# 3KW-139_V1_2SchDoc.net
KiCad netlist of a schematic drawn in Altium Designer
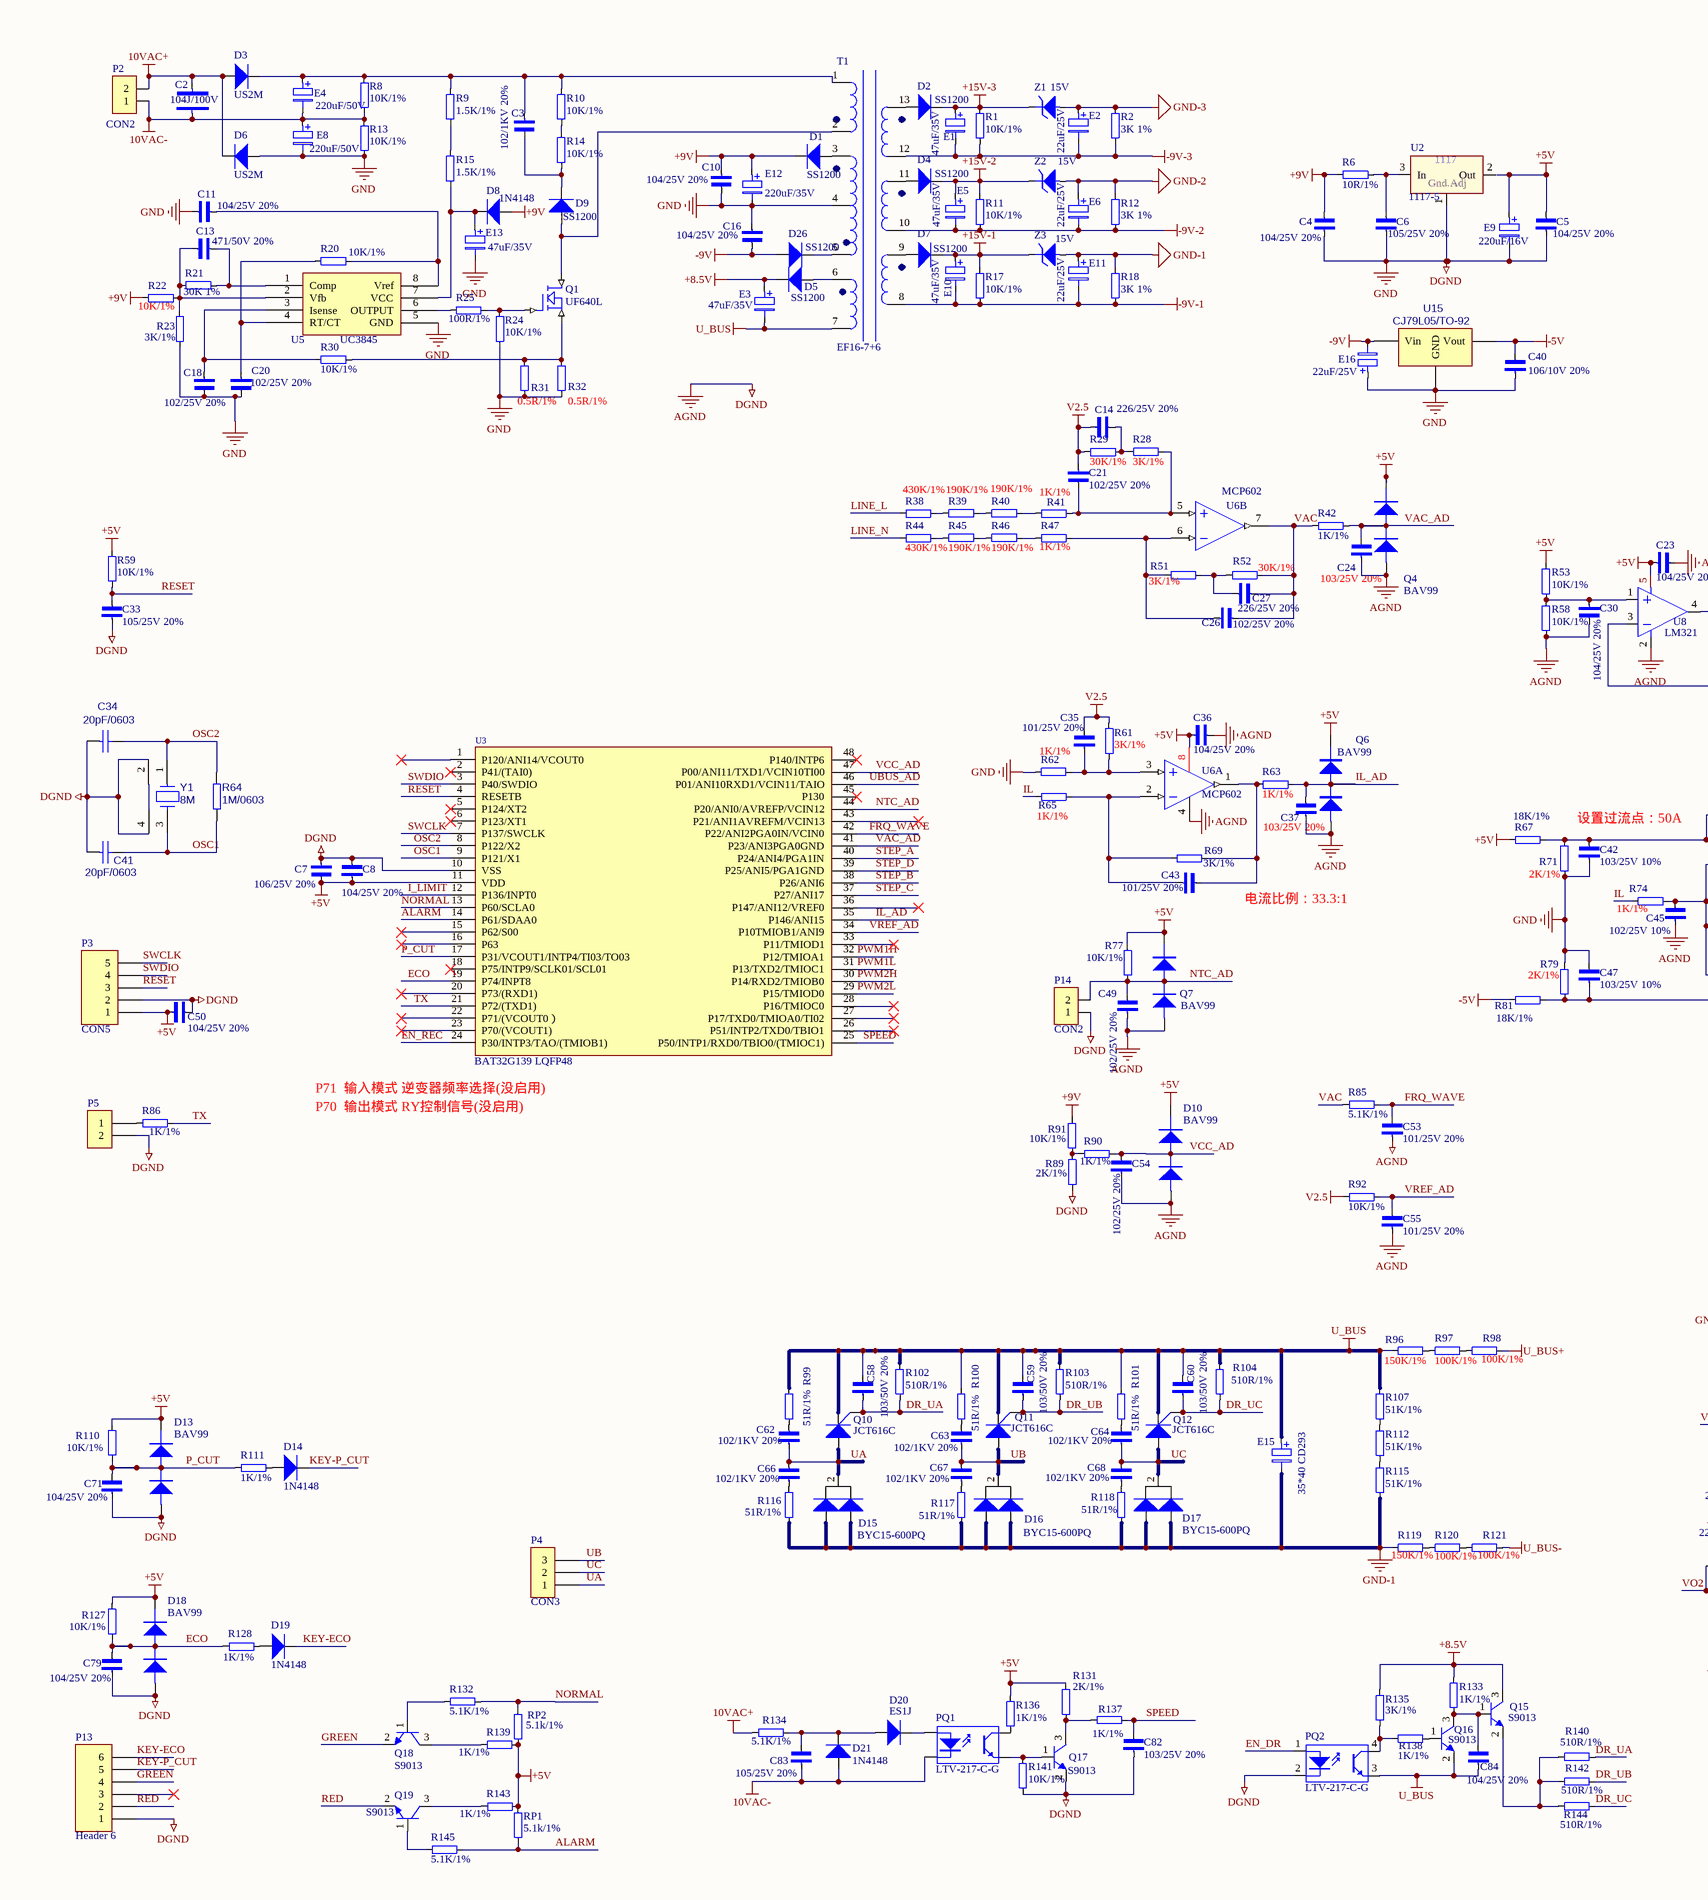
[diagram p0: 3KW-139_V1.2SchDoc.SchDoc, left]
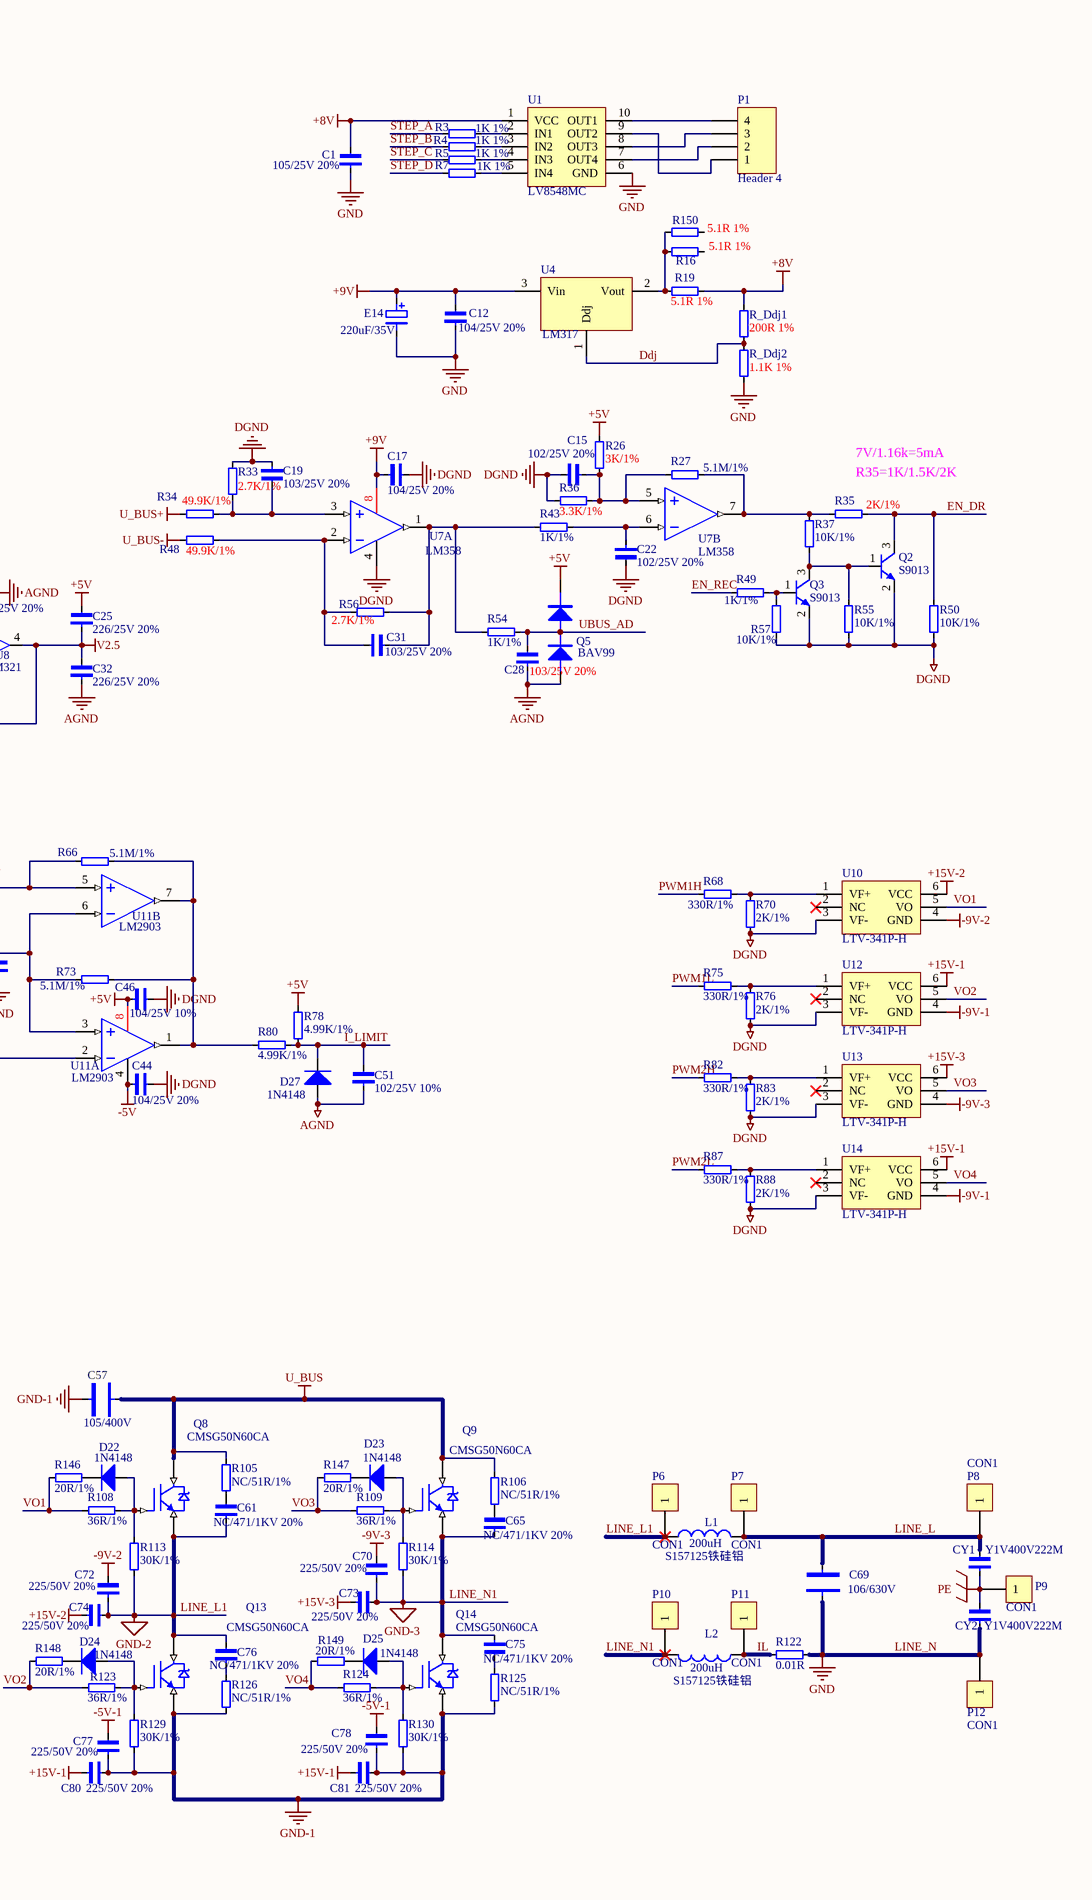
[diagram p1: 3KW-139_V1.2SchDoc.SchDoc, right]

(export (version "E")
  (design (tool "Eeschema 10.0.6"))
  (components
    (comp (ref "C1")
      (value "105/25V 20%")
      (footprint "0603c")
      (description "贴片 无极性电容")
      (libsource (lib "PCB_CMS_139") (part "C_SMD"))
    )
    (comp (ref "C2")
      (value "104J/100V")
      (footprint "104/100V")
      (description "CBB无极性电容")
      (libsource (lib "PCB_CMS_139") (part "CAPACITOR_CBB"))
    )
    (comp (ref "C3")
      (value "102/1KV 20%")
      (footprint "1206C")
      (description "贴片 无极性电容")
      (libsource (lib "PCB_CMS_139") (part "C_SMD"))
    )
    (comp (ref "C4")
      (value "104/25V 20%")
      (footprint "0603c")
      (description "贴片 无极性电容")
      (libsource (lib "PCB_CMS_139") (part "C_SMD"))
    )
    (comp (ref "C5")
      (value "104/25V 20%")
      (footprint "0603c")
      (description "贴片 无极性电容")
      (libsource (lib "PCB_CMS_139") (part "C_SMD"))
    )
    (comp (ref "C6")
      (value "105/25V 20%")
      (footprint "0603c")
      (description "贴片 无极性电容")
      (libsource (lib "PCB_CMS_139") (part "C_SMD"))
    )
    (comp (ref "C7")
      (value "106/25V 20%")
      (footprint "0603c")
      (description "贴片 无极性电容")
      (libsource (lib "PCB_CMS_139") (part "C_SMD"))
    )
    (comp (ref "C8")
      (value "104/25V 20%")
      (footprint "0603c")
      (description "贴片 无极性电容")
      (libsource (lib "PCB_CMS_139") (part "C_SMD"))
    )
    (comp (ref "C10")
      (value "104/25V 20%")
      (footprint "0603C")
      (description "贴片 无极性电容")
      (libsource (lib "PCB_CMS_139") (part "C_SMD"))
    )
    (comp (ref "C11")
      (value "104/25V 20%")
      (footprint "0603C")
      (description "贴片 无极性电容")
      (libsource (lib "PCB_CMS_139") (part "C_SMD"))
    )
    (comp (ref "C12")
      (value "104/25V 20%")
      (footprint "0603c")
      (description "贴片 无极性电容")
      (libsource (lib "PCB_CMS_139") (part "C_SMD"))
    )
    (comp (ref "C13")
      (value "471/50V 20%")
      (footprint "0603C")
      (description "贴片 无极性电容")
      (libsource (lib "PCB_CMS_139") (part "C_SMD"))
    )
    (comp (ref "C14")
      (value "226/25V 20%")
      (footprint "0603c")
      (description "贴片 无极性电容")
      (libsource (lib "PCB_CMS_139") (part "C_SMD"))
    )
    (comp (ref "C15")
      (value "102/25V 20%")
      (footprint "0603c")
      (description "贴片 无极性电容")
      (libsource (lib "PCB_CMS_139") (part "C_SMD"))
    )
    (comp (ref "C16")
      (value "104/25V 20%")
      (footprint "0603C")
      (description "贴片 无极性电容")
      (libsource (lib "PCB_CMS_139") (part "C_SMD"))
    )
    (comp (ref "C17")
      (value "104/25V 20%")
      (footprint "0603c")
      (description "贴片 无极性电容")
      (libsource (lib "PCB_CMS_139") (part "C_SMD"))
    )
    (comp (ref "C18")
      (value "102/25V 20%")
      (footprint "0603C")
      (description "贴片 无极性电容")
      (libsource (lib "PCB_CMS_139") (part "C_SMD"))
    )
    (comp (ref "C19")
      (value "103/25V 20%")
      (footprint "0603c")
      (description "贴片 无极性电容")
      (libsource (lib "PCB_CMS_139") (part "C_SMD"))
    )
    (comp (ref "C20")
      (value "102/25V 20%")
      (footprint "0603C")
      (description "贴片 无极性电容")
      (libsource (lib "PCB_CMS_139") (part "C_SMD"))
    )
    (comp (ref "C21")
      (value "102/25V 20%")
      (footprint "0603c")
      (description "贴片 无极性电容")
      (libsource (lib "PCB_CMS_139") (part "C_SMD"))
    )
    (comp (ref "C22")
      (value "102/25V 20%")
      (footprint "0603c")
      (description "贴片 无极性电容")
      (libsource (lib "PCB_CMS_139") (part "C_SMD"))
    )
    (comp (ref "C23")
      (value "104/25V 20%")
      (footprint "0603c")
      (description "贴片 无极性电容")
      (libsource (lib "PCB_CMS_139") (part "C_SMD"))
    )
    (comp (ref "C24")
      (value "103/25V 20%")
      (footprint "0603c")
      (description "贴片 无极性电容")
      (libsource (lib "PCB_CMS_139") (part "C_SMD"))
    )
    (comp (ref "C25")
      (value "226/25V 20%")
      (footprint "0603c")
      (description "贴片 无极性电容")
      (libsource (lib "PCB_CMS_139") (part "C_SMD"))
    )
    (comp (ref "C26")
      (value "102/25V 20%")
      (footprint "0603c")
      (description "贴片 无极性电容")
      (libsource (lib "PCB_CMS_139") (part "C_SMD"))
    )
    (comp (ref "C27")
      (value "226/25V 20%")
      (footprint "0603c")
      (description "贴片 无极性电容")
      (libsource (lib "PCB_CMS_139") (part "C_SMD"))
    )
    (comp (ref "C28")
      (value "103/25V 20%")
      (footprint "0603c")
      (description "贴片 无极性电容")
      (libsource (lib "PCB_CMS_139") (part "C_SMD"))
    )
    (comp (ref "C30")
      (value "104/25V 20%")
      (footprint "0603c")
      (description "贴片 无极性电容")
      (libsource (lib "PCB_CMS_139") (part "C_SMD"))
    )
    (comp (ref "C31")
      (value "103/25V 20%")
      (footprint "0603c")
      (description "贴片 无极性电容")
      (libsource (lib "PCB_CMS_139") (part "C_SMD"))
    )
    (comp (ref "C32")
      (value "226/25V 20%")
      (footprint "0603c")
      (description "贴片 无极性电容")
      (libsource (lib "PCB_CMS_139") (part "C_SMD"))
    )
    (comp (ref "C33")
      (value "105/25V 20%")
      (footprint "0603c")
      (description "贴片 无极性电容")
      (libsource (lib "PCB_CMS_139") (part "C_SMD"))
    )
    (comp (ref "C34")
      (value "20pF/0603")
      (footprint "C0603")
      (description "Cap")
      (libsource (lib "*") (part "CAP-SMD"))
    )
    (comp (ref "C35")
      (value "101/25V 20%")
      (footprint "0603c")
      (description "贴片 无极性电容")
      (libsource (lib "PCB_CMS_139") (part "C_SMD"))
    )
    (comp (ref "C36")
      (value "104/25V 20%")
      (footprint "0603c")
      (description "贴片 无极性电容")
      (libsource (lib "PCB_CMS_139") (part "C_SMD"))
    )
    (comp (ref "C37")
      (value "103/25V 20%")
      (footprint "0603c")
      (description "贴片 无极性电容")
      (libsource (lib "PCB_CMS_139") (part "C_SMD"))
    )
    (comp (ref "C40")
      (value "106/10V 20%")
      (footprint "0603c")
      (description "贴片 无极性电容")
      (libsource (lib "PCB_CMS_139") (part "C_SMD"))
    )
    (comp (ref "C41")
      (value "20pF/0603")
      (footprint "C0603")
      (description "Cap")
      (libsource (lib "*") (part "CAP-SMD"))
    )
    (comp (ref "C42")
      (value "103/25V 10%")
      (footprint "0603c")
      (description "贴片 无极性电容")
      (libsource (lib "PCB_CMS_139") (part "C_SMD"))
    )
    (comp (ref "C43")
      (value "101/25V 20%")
      (footprint "0603c")
      (description "贴片 无极性电容")
      (libsource (lib "PCB_CMS_139") (part "C_SMD"))
    )
    (comp (ref "C44")
      (value "104/25V 20%")
      (footprint "0603c")
      (description "贴片 无极性电容")
      (libsource (lib "PCB_CMS_139") (part "C_SMD"))
    )
    (comp (ref "C45")
      (value "102/25V 10%")
      (footprint "0603c")
      (description "贴片 无极性电容")
      (libsource (lib "PCB_CMS_139") (part "C_SMD"))
    )
    (comp (ref "C46")
      (value "104/25V 10%")
      (footprint "0603c")
      (description "贴片 无极性电容")
      (libsource (lib "PCB_CMS_139") (part "C_SMD"))
    )
    (comp (ref "C47")
      (value "103/25V 10%")
      (footprint "0603c")
      (description "贴片 无极性电容")
      (libsource (lib "PCB_CMS_139") (part "C_SMD"))
    )
    (comp (ref "C49")
      (value "102/25V 20%")
      (footprint "0603c")
      (description "贴片 无极性电容")
      (libsource (lib "PCB_CMS_139") (part "C_SMD"))
    )
    (comp (ref "C50")
      (value "104/25V 20%")
      (footprint "0603c")
      (description "贴片 无极性电容")
      (libsource (lib "PCB_CMS_139") (part "C_SMD"))
    )
    (comp (ref "C51")
      (value "102/25V 10%")
      (footprint "0603c")
      (description "贴片 无极性电容")
      (libsource (lib "PCB_CMS_139") (part "C_SMD"))
    )
    (comp (ref "C53")
      (value "101/25V 20%")
      (footprint "0603c")
      (description "贴片 无极性电容")
      (libsource (lib "PCB_CMS_139") (part "C_SMD"))
    )
    (comp (ref "C54")
      (value "102/25V 20%")
      (footprint "0603C")
      (description "贴片 无极性电容")
      (libsource (lib "PCB_CMS_139") (part "C_SMD"))
    )
    (comp (ref "C55")
      (value "101/25V 20%")
      (footprint "0603c")
      (description "贴片 无极性电容")
      (libsource (lib "PCB_CMS_139") (part "C_SMD"))
    )
    (comp (ref "C57")
      (value "105/400V")
      (footprint "105/400V-3")
      (description "CBB无极性电容")
      (libsource (lib "PCB_CMS_139") (part "CAPACITOR_CBB"))
    )
    (comp (ref "C58")
      (value "103/50V 20%")
      (footprint "1206C")
      (description "贴片 无极性电容")
      (libsource (lib "PCB_CMS_139") (part "C_SMD"))
    )
    (comp (ref "C59")
      (value "103/50V 20%")
      (footprint "1206C")
      (description "贴片 无极性电容")
      (libsource (lib "PCB_CMS_139") (part "C_SMD"))
    )
    (comp (ref "C60")
      (value "103/50V 20%")
      (footprint "1206C")
      (description "贴片 无极性电容")
      (libsource (lib "PCB_CMS_139") (part "C_SMD"))
    )
    (comp (ref "C61")
      (value "NC/471/1KV 20%")
      (footprint "1206C")
      (description "贴片 无极性电容")
      (libsource (lib "PCB_CMS_139") (part "C_SMD"))
    )
    (comp (ref "C62")
      (value "102/1KV 20%")
      (footprint "1206C")
      (description "贴片 无极性电容")
      (libsource (lib "PCB_CMS_139") (part "C_SMD"))
    )
    (comp (ref "C63")
      (value "102/1KV 20%")
      (footprint "1206C")
      (description "贴片 无极性电容")
      (libsource (lib "PCB_CMS_139") (part "C_SMD"))
    )
    (comp (ref "C64")
      (value "102/1KV 20%")
      (footprint "1206C")
      (description "贴片 无极性电容")
      (libsource (lib "PCB_CMS_139") (part "C_SMD"))
    )
    (comp (ref "C65")
      (value "NC/471/1KV 20%")
      (footprint "1206C")
      (description "贴片 无极性电容")
      (libsource (lib "PCB_CMS_139") (part "C_SMD"))
    )
    (comp (ref "C66")
      (value "102/1KV 20%")
      (footprint "1206C")
      (description "贴片 无极性电容")
      (libsource (lib "PCB_CMS_139") (part "C_SMD"))
    )
    (comp (ref "C67")
      (value "102/1KV 20%")
      (footprint "1206C")
      (description "贴片 无极性电容")
      (libsource (lib "PCB_CMS_139") (part "C_SMD"))
    )
    (comp (ref "C68")
      (value "102/1KV 20%")
      (footprint "1206C")
      (description "贴片 无极性电容")
      (libsource (lib "PCB_CMS_139") (part "C_SMD"))
    )
    (comp (ref "C69")
      (value "106/630V")
      (footprint "106/400V")
      (description "CBB无极性电容")
      (libsource (lib "PCB_CMS_139") (part "CAPACITOR_CBB"))
    )
    (comp (ref "C70")
      (value "225/50V 20%")
      (footprint "1206C")
      (description "贴片 无极性电容")
      (libsource (lib "PCB_CMS_139") (part "C_SMD"))
    )
    (comp (ref "C71")
      (value "104/25V 20%")
      (footprint "0603C")
      (description "贴片 无极性电容")
      (libsource (lib "PCB_CMS_139") (part "C_SMD"))
    )
    (comp (ref "C72")
      (value "225/50V 20%")
      (footprint "1206C")
      (description "贴片 无极性电容")
      (libsource (lib "PCB_CMS_139") (part "C_SMD"))
    )
    (comp (ref "C73")
      (value "225/50V 20%")
      (footprint "1206C")
      (description "贴片 无极性电容")
      (libsource (lib "PCB_CMS_139") (part "C_SMD"))
    )
    (comp (ref "C74")
      (value "225/50V 20%")
      (footprint "1206C")
      (description "贴片 无极性电容")
      (libsource (lib "PCB_CMS_139") (part "C_SMD"))
    )
    (comp (ref "C75")
      (value "NC/471/1KV 20%")
      (footprint "1206C")
      (description "贴片 无极性电容")
      (libsource (lib "PCB_CMS_139") (part "C_SMD"))
    )
    (comp (ref "C76")
      (value "NC/471/1KV 20%")
      (footprint "1206C")
      (description "贴片 无极性电容")
      (libsource (lib "PCB_CMS_139") (part "C_SMD"))
    )
    (comp (ref "C77")
      (value "225/50V 20%")
      (footprint "1206C")
      (description "贴片 无极性电容")
      (libsource (lib "PCB_CMS_139") (part "C_SMD"))
    )
    (comp (ref "C78")
      (value "225/50V 20%")
      (footprint "1206C")
      (description "贴片 无极性电容")
      (libsource (lib "PCB_CMS_139") (part "C_SMD"))
    )
    (comp (ref "C79")
      (value "104/25V 20%")
      (footprint "0603C")
      (description "贴片 无极性电容")
      (libsource (lib "PCB_CMS_139") (part "C_SMD"))
    )
    (comp (ref "C80")
      (value "225/50V 20%")
      (footprint "1206C")
      (description "贴片 无极性电容")
      (libsource (lib "PCB_CMS_139") (part "C_SMD"))
    )
    (comp (ref "C81")
      (value "225/50V 20%")
      (footprint "1206C")
      (description "贴片 无极性电容")
      (libsource (lib "PCB_CMS_139") (part "C_SMD"))
    )
    (comp (ref "C82")
      (value "103/25V 20%")
      (footprint "0603C")
      (description "贴片 无极性电容")
      (libsource (lib "PCB_CMS_139") (part "C_SMD"))
    )
    (comp (ref "C83")
      (value "105/25V 20%")
      (footprint "1206C")
      (description "贴片 无极性电容")
      (libsource (lib "PCB_CMS_139") (part "C_SMD"))
    )
    (comp (ref "C84")
      (value "104/25V 20%")
      (footprint "1206C")
      (description "贴片 无极性电容")
      (libsource (lib "PCB_CMS_139") (part "C_SMD"))
    )
    (comp (ref "CY1")
      (value "Y1V400V222M")
      (footprint "Y1V400")
      (description "贴片 无极性电容")
      (libsource (lib "PCB_CMS_139") (part "C_SMD"))
    )
    (comp (ref "CY2")
      (value "Y1V400V222M")
      (footprint "Y1V400")
      (description "贴片 无极性电容")
      (libsource (lib "PCB_CMS_139") (part "C_SMD"))
    )
    (comp (ref "D1")
      (value "SS1200")
      (footprint "SMA - AK")
      (description "贴片 二极管")
      (libsource (lib "PCB_CMS_139") (part "D_SMD"))
    )
    (comp (ref "D2")
      (value "SS1200")
      (footprint "SMA - AK")
      (description "贴片 二极管")
      (libsource (lib "PCB_CMS_139") (part "D_SMD"))
    )
    (comp (ref "D3")
      (value "US2M")
      (footprint "SMA - AK")
      (description "贴片 二极管")
      (libsource (lib "PCB_CMS_139") (part "D_SMD"))
    )
    (comp (ref "D4")
      (value "SS1200")
      (footprint "SMA - AK")
      (description "贴片 二极管")
      (libsource (lib "PCB_CMS_139") (part "D_SMD"))
    )
    (comp (ref "D5")
      (value "SS1200")
      (footprint "SMA - AK")
      (description "贴片 二极管")
      (libsource (lib "PCB_CMS_139") (part "D_SMD"))
    )
    (comp (ref "D6")
      (value "US2M")
      (footprint "SMA - AK")
      (description "贴片 二极管")
      (libsource (lib "PCB_CMS_139") (part "D_SMD"))
    )
    (comp (ref "D7")
      (value "SS1200")
      (footprint "SMA - AK")
      (description "贴片 二极管")
      (libsource (lib "PCB_CMS_139") (part "D_SMD"))
    )
    (comp (ref "D8")
      (value "1N4148")
      (footprint "SOD-123F")
      (description "贴片 二极管")
      (libsource (lib "PCB_CMS_139") (part "D_SMD"))
    )
    (comp (ref "D9")
      (value "SS1200")
      (footprint "SMA - AK")
      (description "贴片 二极管")
      (libsource (lib "PCB_CMS_139") (part "D_SMD"))
    )
    (comp (ref "D10")
      (value "BAV99")
      (footprint "SOT-23")
      (description "贴片串联双二极管 eg:BAT54S")
      (libsource (lib "PCB_CMS_139") (part "D2-串联"))
    )
    (comp (ref "D13")
      (value "BAV99")
      (footprint "SOT-23")
      (description "贴片串联双二极管 eg:BAT54S")
      (libsource (lib "PCB_CMS_139") (part "D2-串联"))
    )
    (comp (ref "D14")
      (value "1N4148")
      (footprint "SOD-123F")
      (description "贴片 二极管")
      (libsource (lib "PCB_CMS_139") (part "D_SMD"))
    )
    (comp (ref "D15")
      (value "BYC15-600PQ")
      (footprint "TO-220-AC - S")
      (libsource (lib "PCB_CMS_139") (part "DIODE TO-220"))
    )
    (comp (ref "D16")
      (value "BYC15-600PQ")
      (footprint "TO-220-AC - S")
      (libsource (lib "PCB_CMS_139") (part "DIODE TO-220"))
    )
    (comp (ref "D17")
      (value "BYC15-600PQ")
      (footprint "TO-220-AC - S")
      (libsource (lib "PCB_CMS_139") (part "DIODE TO-220"))
    )
    (comp (ref "D18")
      (value "BAV99")
      (footprint "SOT-23")
      (description "贴片串联双二极管 eg:BAT54S")
      (libsource (lib "PCB_CMS_139") (part "D2-串联"))
    )
    (comp (ref "D19")
      (value "1N4148")
      (footprint "SOD-123F")
      (description "贴片 二极管")
      (libsource (lib "PCB_CMS_139") (part "D_SMD"))
    )
    (comp (ref "D20")
      (value "ES1J")
      (footprint "SOD-123F")
      (description "贴片 二极管")
      (libsource (lib "PCB_CMS_139") (part "D_SMD"))
    )
    (comp (ref "D21")
      (value "1N4148")
      (footprint "SOD-123F")
      (description "贴片 二极管")
      (libsource (lib "PCB_CMS_139") (part "D_SMD"))
    )
    (comp (ref "D22")
      (value "1N4148")
      (footprint "SOD-123F")
      (description "贴片 二极管")
      (libsource (lib "PCB_CMS_139") (part "D_SMD"))
    )
    (comp (ref "D23")
      (value "1N4148")
      (footprint "SOD-123F")
      (description "贴片 二极管")
      (libsource (lib "PCB_CMS_139") (part "D_SMD"))
    )
    (comp (ref "D24")
      (value "1N4148")
      (footprint "SOD-123F")
      (description "贴片 二极管")
      (libsource (lib "PCB_CMS_139") (part "D_SMD"))
    )
    (comp (ref "D25")
      (value "1N4148")
      (footprint "SOD-123F")
      (description "贴片 二极管")
      (libsource (lib "PCB_CMS_139") (part "D_SMD"))
    )
    (comp (ref "D26")
      (value "SS1200")
      (footprint "SMA - AK")
      (description "贴片 二极管")
      (libsource (lib "PCB_CMS_139") (part "D_SMD"))
    )
    (comp (ref "D27")
      (value "1N4148")
      (footprint "SOD-123F")
      (description "贴片 二极管")
      (libsource (lib "PCB_CMS_139") (part "D_SMD"))
    )
    (comp (ref "E1")
      (value "47uF/35V")
      (footprint "ECAP-6.3*11")
      (description "直插 电解电容")
      (libsource (lib "motor_sch") (part "E"))
    )
    (comp (ref "E2")
      (value "22uF/25V")
      (footprint "ECAP-5*11")
      (description "直插 电解电容")
      (libsource (lib "motor_sch") (part "E"))
    )
    (comp (ref "E3")
      (value "47uF/35V")
      (footprint "ECAP-6.3*11")
      (description "直插 电解电容")
      (libsource (lib "motor_sch") (part "E"))
    )
    (comp (ref "E4")
      (value "220uF/50V")
      (footprint "10*16")
      (description "直插 电解电容")
      (libsource (lib "motor_sch") (part "E"))
    )
    (comp (ref "E5")
      (value "47uF/35V")
      (footprint "ECAP-6.3*11")
      (description "直插 电解电容")
      (libsource (lib "motor_sch") (part "E"))
    )
    (comp (ref "E6")
      (value "22uF/25V")
      (footprint "ECAP-5*11")
      (description "直插 电解电容")
      (libsource (lib "motor_sch") (part "E"))
    )
    (comp (ref "E8")
      (value "220uF/50V")
      (footprint "10*16")
      (description "直插 电解电容")
      (libsource (lib "motor_sch") (part "E"))
    )
    (comp (ref "E9")
      (value "220uF/16V")
      (footprint "6.3*11")
      (description "直插 电解电容")
      (libsource (lib "motor_sch") (part "E"))
    )
    (comp (ref "E10")
      (value "47uF/35V")
      (footprint "ECAP-6.3*11")
      (description "直插 电解电容")
      (libsource (lib "motor_sch") (part "E"))
    )
    (comp (ref "E11")
      (value "22uF/25V")
      (footprint "ECAP-5*11")
      (description "直插 电解电容")
      (libsource (lib "motor_sch") (part "E"))
    )
    (comp (ref "E12")
      (value "220uF/35V")
      (footprint "8*12")
      (description "直插 电解电容")
      (libsource (lib "motor_sch") (part "E"))
    )
    (comp (ref "E13")
      (value "47uF/35V")
      (footprint "ECAP-6.3*11")
      (description "直插 电解电容")
      (libsource (lib "motor_sch") (part "E"))
    )
    (comp (ref "E14")
      (value "220uF/35V")
      (footprint "EC08F350")
      (description "直插 电解电容")
      (libsource (lib "motor_sch") (part "E"))
    )
    (comp (ref "E15")
      (value "35*40 CD293")
      (footprint "1000uF/250V")
      (description "直插 电解电容 35*40 CD293\r\n120VAC=2200uF/250V\r\n230VAC=330uF/450V")
      (libsource (lib "motor_sch") (part "E"))
    )
    (comp (ref "E16")
      (value "22uF/25V")
      (footprint "ECAP-5*11")
      (description "直插 电解电容")
      (libsource (lib "") (part "E_1"))
    )
    (comp (ref "L1")
      (value "S157125铁硅铝")
      (footprint "L45*45-1-1")
      (description "Inductor")
      (fields (field (name "ALTIUM_VALUE") "200uH") (field (name "PUBLISHER") "Altium Limited"))
      (libsource (lib "Miscellaneous Devices") (part "Inductor"))
    )
    (comp (ref "L2")
      (value "S157125铁硅铝")
      (footprint "L45*45-1-1")
      (description "Inductor")
      (fields (field (name "ALTIUM_VALUE") "200uH") (field (name "PUBLISHER") "Altium Limited"))
      (libsource (lib "Miscellaneous Devices") (part "Inductor"))
    )
    (comp (ref "P1")
      (value "Header 4")
      (footprint "P4-2.8")
      (description "Header, 4-Pin")
      (fields (field (name "PUBLISHER") "Altium Limited"))
      (libsource (lib "motor_sch-2017-6-15") (part "Header 4"))
    )
    (comp (ref "P2") (value "CON2") (footprint "DJ7021A-2.8-11") (libsource (lib "SCH") (part "CON2")))
    (comp (ref "P3")
      (value "CON5")
      (footprint "HDR1X5")
      (description "Header, 5-Pin")
      (fields (field (name "PUBLISHER") "Altium Limited"))
      (libsource (lib "motor_sch-2017-6-15") (part "Header 5"))
    )
    (comp (ref "P4") (value "CON3") (footprint "DJ3071A-6.3-11") (libsource (lib "SCH") (part "CON3")))
    (comp (ref "P5")
      (value "~")
      (footprint "mixic_motor_Library_V1.1:HDR1X2")
      (description "Connector, 2Pin")
      (libsource (lib "Gpower_Altium") (part "CON2P"))
    )
    (comp (ref "P6") (value "CON1") (footprint "HOLE1.0") (libsource (lib "SCH") (part "CON1")))
    (comp (ref "P7") (value "CON1") (footprint "HOLE1.0") (libsource (lib "SCH") (part "CON1")))
    (comp (ref "P8") (value "CON1") (footprint "HOLE2.5") (libsource (lib "SCH") (part "CON1")))
    (comp (ref "P9") (value "CON1") (footprint "HOLE1.6") (libsource (lib "") (part "CON1_1")))
    (comp (ref "P10") (value "CON1") (footprint "HOLE1.0") (libsource (lib "SCH") (part "CON1")))
    (comp (ref "P11") (value "CON1") (footprint "HOLE1.0") (libsource (lib "SCH") (part "CON1")))
    (comp (ref "P12") (value "CON1") (footprint "HOLE2.5") (libsource (lib "") (part "CON1_2")))
    (comp (ref "P13")
      (value "Header 6")
      (footprint "P6-2.8")
      (description "Header, 5-Pin")
      (fields (field (name "PUBLISHER") "Altium Limited"))
      (libsource (lib "motor_sch-2017-6-15") (part "Header 6"))
    )
    (comp (ref "P14") (value "CON2") (footprint "HDR1X2") (libsource (lib "SCH") (part "CON2")))
    (comp (ref "PQ1")
      (value "LTV-217-C-G")
      (footprint "SOP-4-P1.27")
      (description "光藕-PC817,PC357")
      (libsource (lib "GCE-SCH(2014.02.14)") (part "OPTO-817"))
    )
    (comp (ref "PQ2")
      (value "LTV-217-C-G")
      (footprint "SOP-4-P1.27")
      (description "光藕-PC817,PC357")
      (libsource (lib "") (part "OPTO-817_1"))
    )
    (comp (ref "Q1")
      (value "UF640L")
      (footprint "TO-220")
      (description "MOSFET")
      (libsource (lib "motor_sch-2017-6-15") (part "MOS-N"))
    )
    (comp (ref "Q2")
      (value "S9013")
      (footprint "S8050")
      (description "NPN")
      (libsource (lib "motor_sch-2017-6-15") (part "S8050"))
    )
    (comp (ref "Q3")
      (value "S9013")
      (footprint "S8050")
      (description "NPN")
      (libsource (lib "motor_sch-2017-6-15") (part "S8050"))
    )
    (comp (ref "Q4") (value "BAV99") (footprint "SOT-23") (libsource (lib "SCH") (part "BAV99")))
    (comp (ref "Q5") (value "BAV99") (footprint "SOT-23") (libsource (lib "SCH") (part "BAV99")))
    (comp (ref "Q6") (value "BAV99") (footprint "SOT-23") (libsource (lib "SCH") (part "BAV99")))
    (comp (ref "Q7") (value "BAV99") (footprint "SOT-23") (libsource (lib "SCH") (part "BAV99")))
    (comp (ref "Q8") (value "CMSG50N60CA") (footprint "to-247-1-1") (libsource (lib "Schlib1") (part "IGBT")))
    (comp (ref "Q9") (value "CMSG50N60CA") (footprint "to-247-1-1") (libsource (lib "Schlib1") (part "IGBT")))
    (comp (ref "Q10")
      (value "JCT616C")
      (footprint "TO-220-AB1 - S")
      (libsource (lib "PCB_CMS_139") (part "TYN625"))
    )
    (comp (ref "Q11")
      (value "JCT616C")
      (footprint "TO-220-AB1 - S")
      (libsource (lib "PCB_CMS_139") (part "TYN625"))
    )
    (comp (ref "Q12")
      (value "JCT616C")
      (footprint "TO-220-AB1 - S")
      (libsource (lib "PCB_CMS_139") (part "TYN625"))
    )
    (comp (ref "Q13")
      (value "CMSG50N60CA")
      (footprint "to-247-1-1")
      (libsource (lib "Schlib1") (part "IGBT"))
    )
    (comp (ref "Q14")
      (value "CMSG50N60CA")
      (footprint "to-247-1-1")
      (libsource (lib "Schlib1") (part "IGBT"))
    )
    (comp (ref "Q15")
      (value "S9013")
      (footprint "S8050")
      (description "NPN")
      (libsource (lib "motor_sch-2017-6-15") (part "S8050"))
    )
    (comp (ref "Q16")
      (value "S9013")
      (footprint "S8050")
      (description "NPN")
      (libsource (lib "motor_sch-2017-6-15") (part "S8050"))
    )
    (comp (ref "Q17")
      (value "S9013")
      (footprint "S8050")
      (description "NPN")
      (libsource (lib "motor_sch-2017-6-15") (part "S8050"))
    )
    (comp (ref "Q18")
      (value "S9013")
      (footprint "S8050")
      (description "NPN")
      (libsource (lib "motor_sch-2017-6-15") (part "S8050"))
    )
    (comp (ref "Q19")
      (value "S9013")
      (footprint "S8050")
      (description "NPN")
      (libsource (lib "motor_sch-2017-6-15") (part "S8050"))
    )
    (comp (ref "R1")
      (value "10K/1%")
      (footprint "0603R")
      (description "贴片 电阻器")
      (libsource (lib "PCB_CMS_139") (part "R_SMD"))
    )
    (comp (ref "R2")
      (value "3K 1%")
      (footprint "0603R")
      (description "贴片 电阻器")
      (libsource (lib "PCB_CMS_139") (part "R_SMD"))
    )
    (comp (ref "R3")
      (value "1K 1%")
      (footprint "0603R")
      (description "贴片 电阻器")
      (libsource (lib "PCB_CMS_139") (part "R_SMD"))
    )
    (comp (ref "R4")
      (value "1K 1%")
      (footprint "0603R")
      (description "贴片 电阻器")
      (libsource (lib "PCB_CMS_139") (part "R_SMD"))
    )
    (comp (ref "R5")
      (value "1K 1%")
      (footprint "0603R")
      (description "贴片 电阻器")
      (libsource (lib "PCB_CMS_139") (part "R_SMD"))
    )
    (comp (ref "R6")
      (value "10R/1%")
      (footprint "0603R")
      (description "贴片 电阻器")
      (libsource (lib "PCB_CMS_139") (part "R_SMD"))
    )
    (comp (ref "R7")
      (value "1K 1%")
      (footprint "0603R")
      (description "贴片 电阻器")
      (libsource (lib "PCB_CMS_139") (part "R_SMD"))
    )
    (comp (ref "R8")
      (value "10K/1%")
      (footprint "0603R")
      (description "贴片 电阻器")
      (libsource (lib "PCB_CMS_139") (part "R_SMD"))
    )
    (comp (ref "R9")
      (value "1.5K/1%")
      (footprint "1206R")
      (description "贴片 电阻器")
      (libsource (lib "PCB_CMS_139") (part "R_SMD"))
    )
    (comp (ref "R10")
      (value "10K/1%")
      (footprint "1206R")
      (description "贴片 电阻器")
      (libsource (lib "PCB_CMS_139") (part "R_SMD"))
    )
    (comp (ref "R11")
      (value "10K/1%")
      (footprint "0603R")
      (description "贴片 电阻器")
      (libsource (lib "PCB_CMS_139") (part "R_SMD"))
    )
    (comp (ref "R12")
      (value "3K 1%")
      (footprint "0603R")
      (description "贴片 电阻器")
      (libsource (lib "PCB_CMS_139") (part "R_SMD"))
    )
    (comp (ref "R13")
      (value "10K/1%")
      (footprint "0603R")
      (description "贴片 电阻器")
      (libsource (lib "PCB_CMS_139") (part "R_SMD"))
    )
    (comp (ref "R14")
      (value "10K/1%")
      (footprint "1206R")
      (description "贴片 电阻器")
      (libsource (lib "PCB_CMS_139") (part "R_SMD"))
    )
    (comp (ref "R15")
      (value "1.5K/1%")
      (footprint "1206R")
      (description "贴片 电阻器")
      (libsource (lib "PCB_CMS_139") (part "R_SMD"))
    )
    (comp (ref "R16")
      (value "5.1R 1%")
      (footprint "1206R")
      (description "贴片 电阻器")
      (libsource (lib "PCB_CMS_139") (part "R_SMD"))
    )
    (comp (ref "R17")
      (value "10K/1%")
      (footprint "0603R")
      (description "贴片 电阻器")
      (libsource (lib "PCB_CMS_139") (part "R_SMD"))
    )
    (comp (ref "R18")
      (value "3K 1%")
      (footprint "0603R")
      (description "贴片 电阻器")
      (libsource (lib "PCB_CMS_139") (part "R_SMD"))
    )
    (comp (ref "R19")
      (value "5.1R 1%")
      (footprint "1206R")
      (description "贴片 电阻器")
      (libsource (lib "PCB_CMS_139") (part "R_SMD"))
    )
    (comp (ref "R20")
      (value "10K/1%")
      (footprint "0603R")
      (description "贴片 电阻器")
      (libsource (lib "PCB_CMS_139") (part "R_SMD"))
    )
    (comp (ref "R21")
      (value "30K 1%")
      (footprint "0603R")
      (description "贴片 电阻器")
      (libsource (lib "PCB_CMS_139") (part "R_SMD"))
    )
    (comp (ref "R22")
      (value "10K/1%")
      (footprint "0603R")
      (description "贴片 电阻器")
      (libsource (lib "PCB_CMS_139") (part "R_SMD"))
    )
    (comp (ref "R23")
      (value "3K/1%")
      (footprint "0603R")
      (description "贴片 电阻器")
      (libsource (lib "PCB_CMS_139") (part "R_SMD"))
    )
    (comp (ref "R24")
      (value "10K/1%")
      (footprint "0603R")
      (description "贴片 电阻器")
      (libsource (lib "PCB_CMS_139") (part "R_SMD"))
    )
    (comp (ref "R25")
      (value "100R/1%")
      (footprint "0603R")
      (description "贴片 电阻器")
      (libsource (lib "PCB_CMS_139") (part "R_SMD"))
    )
    (comp (ref "R26")
      (value "3K/1%")
      (footprint "0603R")
      (description "贴片 电阻器")
      (libsource (lib "PCB_CMS_139") (part "R_SMD"))
    )
    (comp (ref "R27")
      (value "5.1M/1%")
      (footprint "0603R")
      (description "贴片 电阻器")
      (libsource (lib "PCB_CMS_139") (part "R_SMD"))
    )
    (comp (ref "R28")
      (value "3K/1%")
      (footprint "0603R")
      (description "贴片 电阻器")
      (libsource (lib "PCB_CMS_139") (part "R_SMD"))
    )
    (comp (ref "R29")
      (value "30K/1%")
      (footprint "0603R")
      (description "贴片 电阻器")
      (libsource (lib "PCB_CMS_139") (part "R_SMD"))
    )
    (comp (ref "R30")
      (value "10K/1%")
      (footprint "0603R")
      (description "贴片 电阻器")
      (libsource (lib "PCB_CMS_139") (part "R_SMD"))
    )
    (comp (ref "R31")
      (value "0.5R/1%")
      (footprint "1206R")
      (description "贴片 电阻器")
      (libsource (lib "PCB_CMS_139") (part "R_SMD"))
    )
    (comp (ref "R32")
      (value "0.5R/1%")
      (footprint "1206R")
      (description "贴片 电阻器")
      (libsource (lib "PCB_CMS_139") (part "R_SMD"))
    )
    (comp (ref "R33")
      (value "2.7K/1%")
      (footprint "0603R")
      (description "贴片 电阻器")
      (libsource (lib "PCB_CMS_139") (part "R_SMD"))
    )
    (comp (ref "R34")
      (value "49.9K/1%")
      (footprint "0603R")
      (description "贴片 电阻器")
      (libsource (lib "PCB_CMS_139") (part "R_SMD"))
    )
    (comp (ref "R35")
      (value "2K/1%")
      (footprint "0603R")
      (description "贴片 电阻器")
      (libsource (lib "PCB_CMS_139") (part "R_SMD"))
    )
    (comp (ref "R36")
      (value "3.3K/1%")
      (footprint "0603R")
      (description "贴片 电阻器")
      (libsource (lib "PCB_CMS_139") (part "R_SMD"))
    )
    (comp (ref "R37")
      (value "10K/1%")
      (footprint "0603R")
      (description "贴片 电阻器")
      (libsource (lib "PCB_CMS_139") (part "R_SMD"))
    )
    (comp (ref "R38")
      (value "430K/1%")
      (footprint "1206R")
      (description "贴片 电阻器")
      (libsource (lib "PCB_CMS_139") (part "R_SMD"))
    )
    (comp (ref "R39")
      (value "190K/1%")
      (footprint "1206R")
      (description "贴片 电阻器")
      (libsource (lib "PCB_CMS_139") (part "R_SMD"))
    )
    (comp (ref "R40")
      (value "190K/1%")
      (footprint "1206R")
      (description "贴片 电阻器")
      (libsource (lib "PCB_CMS_139") (part "R_SMD"))
    )
    (comp (ref "R41")
      (value "1K/1%")
      (footprint "0603R")
      (description "贴片 电阻器")
      (libsource (lib "PCB_CMS_139") (part "R_SMD"))
    )
    (comp (ref "R42")
      (value "1K/1%")
      (footprint "0603R")
      (description "贴片 电阻器")
      (libsource (lib "PCB_CMS_139") (part "R_SMD"))
    )
    (comp (ref "R43")
      (value "1K/1%")
      (footprint "0603R")
      (description "贴片 电阻器")
      (libsource (lib "PCB_CMS_139") (part "R_SMD"))
    )
    (comp (ref "R44")
      (value "430K/1%")
      (footprint "1206R")
      (description "贴片 电阻器")
      (libsource (lib "PCB_CMS_139") (part "R_SMD"))
    )
    (comp (ref "R45")
      (value "190K/1%")
      (footprint "1206R")
      (description "贴片 电阻器")
      (libsource (lib "PCB_CMS_139") (part "R_SMD"))
    )
    (comp (ref "R46")
      (value "190K/1%")
      (footprint "1206R")
      (description "贴片 电阻器")
      (libsource (lib "PCB_CMS_139") (part "R_SMD"))
    )
    (comp (ref "R47")
      (value "1K/1%")
      (footprint "0603R")
      (description "贴片 电阻器")
      (libsource (lib "PCB_CMS_139") (part "R_SMD"))
    )
    (comp (ref "R48")
      (value "49.9K/1%")
      (footprint "0603R")
      (description "贴片 电阻器")
      (libsource (lib "PCB_CMS_139") (part "R_SMD"))
    )
    (comp (ref "R49")
      (value "1K/1%")
      (footprint "0603R")
      (description "贴片 电阻器")
      (libsource (lib "PCB_CMS_139") (part "R_SMD"))
    )
    (comp (ref "R50")
      (value "10K/1%")
      (footprint "0603R")
      (description "贴片 电阻器")
      (libsource (lib "PCB_CMS_139") (part "R_SMD"))
    )
    (comp (ref "R51")
      (value "3K/1%")
      (footprint "0603R")
      (description "贴片 电阻器")
      (libsource (lib "PCB_CMS_139") (part "R_SMD"))
    )
    (comp (ref "R52")
      (value "30K/1%")
      (footprint "0603R")
      (description "贴片 电阻器")
      (libsource (lib "PCB_CMS_139") (part "R_SMD"))
    )
    (comp (ref "R53")
      (value "10K/1%")
      (footprint "0603R")
      (description "贴片 电阻器")
      (libsource (lib "PCB_CMS_139") (part "R_SMD"))
    )
    (comp (ref "R54")
      (value "1K/1%")
      (footprint "0603R")
      (description "贴片 电阻器")
      (libsource (lib "PCB_CMS_139") (part "R_SMD"))
    )
    (comp (ref "R55")
      (value "10K/1%")
      (footprint "0603R")
      (description "贴片 电阻器")
      (libsource (lib "PCB_CMS_139") (part "R_SMD"))
    )
    (comp (ref "R56")
      (value "2.7K/1%")
      (footprint "0603R")
      (description "贴片 电阻器")
      (libsource (lib "PCB_CMS_139") (part "R_SMD"))
    )
    (comp (ref "R57")
      (value "10K/1%")
      (footprint "0603R")
      (description "贴片 电阻器")
      (libsource (lib "PCB_CMS_139") (part "R_SMD"))
    )
    (comp (ref "R58")
      (value "10K/1%")
      (footprint "0603R")
      (description "贴片 电阻器")
      (libsource (lib "PCB_CMS_139") (part "R_SMD"))
    )
    (comp (ref "R59")
      (value "10K/1%")
      (footprint "0603R")
      (description "贴片 电阻器")
      (libsource (lib "PCB_CMS_139") (part "R_SMD"))
    )
    (comp (ref "R61")
      (value "3K/1%")
      (footprint "0603R")
      (description "贴片 电阻器")
      (libsource (lib "PCB_CMS_139") (part "R_SMD"))
    )
    (comp (ref "R62")
      (value "1K/1%")
      (footprint "0603R")
      (description "贴片 电阻器")
      (libsource (lib "PCB_CMS_139") (part "R_SMD"))
    )
    (comp (ref "R63")
      (value "1K/1%")
      (footprint "0603R")
      (description "贴片 电阻器")
      (libsource (lib "PCB_CMS_139") (part "R_SMD"))
    )
    (comp (ref "R64")
      (value "1M/0603")
      (footprint "R0603")
      (description "SMD")
      (libsource (lib "*") (part "RES-SMD"))
    )
    (comp (ref "R65")
      (value "1K/1%")
      (footprint "0603R")
      (description "贴片 电阻器")
      (libsource (lib "PCB_CMS_139") (part "R_SMD"))
    )
    (comp (ref "R66")
      (value "5.1M/1%")
      (footprint "0603R")
      (description "贴片 电阻器")
      (libsource (lib "PCB_CMS_139") (part "R_SMD"))
    )
    (comp (ref "R67")
      (value "18K/1%")
      (footprint "0603R")
      (description "贴片 电阻器")
      (libsource (lib "PCB_CMS_139") (part "R_SMD"))
    )
    (comp (ref "R68")
      (value "330R/1%")
      (footprint "0603R")
      (description "贴片 电阻器")
      (libsource (lib "PCB_CMS_139") (part "R_SMD"))
    )
    (comp (ref "R69")
      (value "3K/1%")
      (footprint "0603R")
      (description "贴片 电阻器")
      (libsource (lib "PCB_CMS_139") (part "R_SMD"))
    )
    (comp (ref "R70")
      (value "2K/1%")
      (footprint "0603R")
      (description "贴片 电阻器")
      (libsource (lib "PCB_CMS_139") (part "R_SMD"))
    )
    (comp (ref "R71")
      (value "2K/1%")
      (footprint "0603R")
      (description "贴片 电阻器")
      (libsource (lib "PCB_CMS_139") (part "R_SMD"))
    )
    (comp (ref "R73")
      (value "5.1M/1%")
      (footprint "0603R")
      (description "贴片 电阻器")
      (libsource (lib "PCB_CMS_139") (part "R_SMD"))
    )
    (comp (ref "R74")
      (value "1K/1%")
      (footprint "0603R")
      (description "贴片 电阻器")
      (libsource (lib "PCB_CMS_139") (part "R_SMD"))
    )
    (comp (ref "R75")
      (value "330R/1%")
      (footprint "0603R")
      (description "贴片 电阻器")
      (libsource (lib "PCB_CMS_139") (part "R_SMD"))
    )
    (comp (ref "R76")
      (value "2K/1%")
      (footprint "0603R")
      (description "贴片 电阻器")
      (libsource (lib "PCB_CMS_139") (part "R_SMD"))
    )
    (comp (ref "R77")
      (value "10K/1%")
      (footprint "0603R")
      (description "贴片 电阻器")
      (libsource (lib "PCB_CMS_139") (part "R_SMD"))
    )
    (comp (ref "R78")
      (value "4.99K/1%")
      (footprint "0603R")
      (description "贴片 电阻器")
      (libsource (lib "PCB_CMS_139") (part "R_SMD"))
    )
    (comp (ref "R79")
      (value "2K/1%")
      (footprint "0603R")
      (description "贴片 电阻器")
      (libsource (lib "PCB_CMS_139") (part "R_SMD"))
    )
    (comp (ref "R80")
      (value "4.99K/1%")
      (footprint "0603R")
      (description "贴片 电阻器")
      (libsource (lib "PCB_CMS_139") (part "R_SMD"))
    )
    (comp (ref "R81")
      (value "18K/1%")
      (footprint "0603R")
      (description "贴片 电阻器")
      (libsource (lib "PCB_CMS_139") (part "R_SMD"))
    )
    (comp (ref "R82")
      (value "330R/1%")
      (footprint "0603R")
      (description "贴片 电阻器")
      (libsource (lib "PCB_CMS_139") (part "R_SMD"))
    )
    (comp (ref "R83")
      (value "2K/1%")
      (footprint "0603R")
      (description "贴片 电阻器")
      (libsource (lib "PCB_CMS_139") (part "R_SMD"))
    )
    (comp (ref "R85")
      (value "5.1K/1%")
      (footprint "0603R")
      (description "贴片 电阻器")
      (libsource (lib "PCB_CMS_139") (part "R_SMD"))
    )
    (comp (ref "R86")
      (value "1K/1%")
      (footprint "0603R")
      (description "贴片 电阻器")
      (libsource (lib "PCB_CMS_139") (part "R_SMD"))
    )
    (comp (ref "R87")
      (value "330R/1%")
      (footprint "0603R")
      (description "贴片 电阻器")
      (libsource (lib "PCB_CMS_139") (part "R_SMD"))
    )
    (comp (ref "R88")
      (value "2K/1%")
      (footprint "0603R")
      (description "贴片 电阻器")
      (libsource (lib "PCB_CMS_139") (part "R_SMD"))
    )
    (comp (ref "R89")
      (value "2K/1%")
      (footprint "0603R")
      (description "贴片 电阻器")
      (libsource (lib "PCB_CMS_139") (part "R_SMD"))
    )
    (comp (ref "R90")
      (value "1K/1%")
      (footprint "0603R")
      (description "贴片 电阻器")
      (libsource (lib "PCB_CMS_139") (part "R_SMD"))
    )
    (comp (ref "R91")
      (value "10K/1%")
      (footprint "0603R")
      (description "贴片 电阻器")
      (libsource (lib "PCB_CMS_139") (part "R_SMD"))
    )
    (comp (ref "R92")
      (value "10K/1%")
      (footprint "0603R")
      (description "贴片 电阻器")
      (libsource (lib "PCB_CMS_139") (part "R_SMD"))
    )
    (comp (ref "R96")
      (value "150K/1%")
      (footprint "1206R")
      (description "贴片 电阻器")
      (libsource (lib "PCB_CMS_139") (part "R_SMD"))
    )
    (comp (ref "R97")
      (value "100K/1%")
      (footprint "1206R")
      (description "贴片 电阻器")
      (libsource (lib "PCB_CMS_139") (part "R_SMD"))
    )
    (comp (ref "R98")
      (value "100K/1%")
      (footprint "1206R")
      (description "贴片 电阻器")
      (libsource (lib "PCB_CMS_139") (part "R_SMD"))
    )
    (comp (ref "R99")
      (value "51R/1%")
      (footprint "1206R")
      (description "贴片 电阻器")
      (libsource (lib "PCB_CMS_139") (part "R_SMD"))
    )
    (comp (ref "R100")
      (value "51R/1%")
      (footprint "1206R")
      (description "贴片 电阻器")
      (libsource (lib "PCB_CMS_139") (part "R_SMD"))
    )
    (comp (ref "R101")
      (value "51R/1%")
      (footprint "1206R")
      (description "贴片 电阻器")
      (libsource (lib "PCB_CMS_139") (part "R_SMD"))
    )
    (comp (ref "R102")
      (value "510R/1%")
      (footprint "1206R")
      (description "贴片 电阻器")
      (libsource (lib "PCB_CMS_139") (part "R_SMD"))
    )
    (comp (ref "R103")
      (value "510R/1%")
      (footprint "1206R")
      (description "贴片 电阻器")
      (libsource (lib "PCB_CMS_139") (part "R_SMD"))
    )
    (comp (ref "R104")
      (value "510R/1%")
      (footprint "1206R")
      (description "贴片 电阻器")
      (libsource (lib "PCB_CMS_139") (part "R_SMD"))
    )
    (comp (ref "R105")
      (value "NC/51R/1%")
      (footprint "2512R")
      (description "贴片 电阻器")
      (libsource (lib "PCB_CMS_139") (part "R_SMD"))
    )
    (comp (ref "R106")
      (value "NC/51R/1%")
      (footprint "2512R")
      (description "贴片 电阻器")
      (libsource (lib "PCB_CMS_139") (part "R_SMD"))
    )
    (comp (ref "R107")
      (value "51K/1%")
      (footprint "1206R")
      (description "贴片 电阻器")
      (libsource (lib "PCB_CMS_139") (part "R_SMD"))
    )
    (comp (ref "R108")
      (value "36R/1%")
      (footprint "1206R")
      (description "贴片 电阻器")
      (libsource (lib "PCB_CMS_139") (part "R_SMD"))
    )
    (comp (ref "R109")
      (value "36R/1%")
      (footprint "1206R")
      (description "贴片 电阻器")
      (libsource (lib "PCB_CMS_139") (part "R_SMD"))
    )
    (comp (ref "R110")
      (value "10K/1%")
      (footprint "0603R")
      (description "贴片 电阻器")
      (libsource (lib "PCB_CMS_139") (part "R_SMD"))
    )
    (comp (ref "R111")
      (value "1K/1%")
      (footprint "0603R")
      (description "贴片 电阻器")
      (libsource (lib "PCB_CMS_139") (part "R_SMD"))
    )
    (comp (ref "R112")
      (value "51K/1%")
      (footprint "1206R")
      (description "贴片 电阻器")
      (libsource (lib "PCB_CMS_139") (part "R_SMD"))
    )
    (comp (ref "R113")
      (value "30K/1%")
      (footprint "0603R")
      (description "贴片 电阻器")
      (libsource (lib "PCB_CMS_139") (part "R_SMD"))
    )
    (comp (ref "R114")
      (value "30K/1%")
      (footprint "0603R")
      (description "贴片 电阻器")
      (libsource (lib "PCB_CMS_139") (part "R_SMD"))
    )
    (comp (ref "R115")
      (value "51K/1%")
      (footprint "1206R")
      (description "贴片 电阻器")
      (libsource (lib "PCB_CMS_139") (part "R_SMD"))
    )
    (comp (ref "R116")
      (value "51R/1%")
      (footprint "1206R")
      (description "贴片 电阻器")
      (libsource (lib "PCB_CMS_139") (part "R_SMD"))
    )
    (comp (ref "R117")
      (value "51R/1%")
      (footprint "1206R")
      (description "贴片 电阻器")
      (libsource (lib "PCB_CMS_139") (part "R_SMD"))
    )
    (comp (ref "R118")
      (value "51R/1%")
      (footprint "1206R")
      (description "贴片 电阻器")
      (libsource (lib "PCB_CMS_139") (part "R_SMD"))
    )
    (comp (ref "R119")
      (value "150K/1%")
      (footprint "1206R")
      (description "贴片 电阻器")
      (libsource (lib "PCB_CMS_139") (part "R_SMD"))
    )
    (comp (ref "R120")
      (value "100K/1%")
      (footprint "1206R")
      (description "贴片 电阻器")
      (libsource (lib "PCB_CMS_139") (part "R_SMD"))
    )
    (comp (ref "R121")
      (value "100K/1%")
      (footprint "1206R")
      (description "贴片 电阻器")
      (libsource (lib "PCB_CMS_139") (part "R_SMD"))
    )
    (comp (ref "R122")
      (value "0.01R")
      (footprint "0.01R 5WS 水泥电阻")
      (description "贴片 电阻器")
      (libsource (lib "PCB_CMS_139") (part "R_SMD"))
    )
    (comp (ref "R123")
      (value "36R/1%")
      (footprint "1206R")
      (description "贴片 电阻器")
      (libsource (lib "PCB_CMS_139") (part "R_SMD"))
    )
    (comp (ref "R124")
      (value "36R/1%")
      (footprint "1206R")
      (description "贴片 电阻器")
      (libsource (lib "PCB_CMS_139") (part "R_SMD"))
    )
    (comp (ref "R125")
      (value "NC/51R/1%")
      (footprint "2512R")
      (description "贴片 电阻器")
      (libsource (lib "PCB_CMS_139") (part "R_SMD"))
    )
    (comp (ref "R126")
      (value "NC/51R/1%")
      (footprint "2512R")
      (description "贴片 电阻器")
      (libsource (lib "PCB_CMS_139") (part "R_SMD"))
    )
    (comp (ref "R127")
      (value "10K/1%")
      (footprint "0603R")
      (description "贴片 电阻器")
      (libsource (lib "PCB_CMS_139") (part "R_SMD"))
    )
    (comp (ref "R128")
      (value "1K/1%")
      (footprint "0603R")
      (description "贴片 电阻器")
      (libsource (lib "PCB_CMS_139") (part "R_SMD"))
    )
    (comp (ref "R129")
      (value "30K/1%")
      (footprint "0603R")
      (description "贴片 电阻器")
      (libsource (lib "PCB_CMS_139") (part "R_SMD"))
    )
    (comp (ref "R130")
      (value "30K/1%")
      (footprint "0603R")
      (description "贴片 电阻器")
      (libsource (lib "PCB_CMS_139") (part "R_SMD"))
    )
    (comp (ref "R131")
      (value "2K/1%")
      (footprint "0603R")
      (description "贴片 电阻器")
      (libsource (lib "PCB_CMS_139") (part "R_SMD"))
    )
    (comp (ref "R132")
      (value "5.1K/1%")
      (footprint "0603R")
      (description "贴片 电阻器")
      (libsource (lib "PCB_CMS_139") (part "R_SMD"))
    )
    (comp (ref "R133")
      (value "1K/1%")
      (footprint "0603R")
      (description "贴片 电阻器")
      (libsource (lib "PCB_CMS_139") (part "R_SMD"))
    )
    (comp (ref "R134")
      (value "5.1K/1%")
      (footprint "0603R")
      (description "贴片 电阻器")
      (libsource (lib "PCB_CMS_139") (part "R_SMD"))
    )
    (comp (ref "R135")
      (value "3K/1%")
      (footprint "0603R")
      (description "贴片 电阻器")
      (libsource (lib "PCB_CMS_139") (part "R_SMD"))
    )
    (comp (ref "R136")
      (value "1K/1%")
      (footprint "0603R")
      (description "贴片 电阻器")
      (libsource (lib "PCB_CMS_139") (part "R_SMD"))
    )
    (comp (ref "R137")
      (value "1K/1%")
      (footprint "0603R")
      (description "贴片 电阻器")
      (libsource (lib "PCB_CMS_139") (part "R_SMD"))
    )
    (comp (ref "R138")
      (value "1K/1%")
      (footprint "0603R")
      (description "贴片 电阻器")
      (libsource (lib "PCB_CMS_139") (part "R_SMD"))
    )
    (comp (ref "R139")
      (value "1K/1%")
      (footprint "0603R")
      (description "贴片 电阻器")
      (libsource (lib "PCB_CMS_139") (part "R_SMD"))
    )
    (comp (ref "R140")
      (value "510R/1%")
      (footprint "1206R")
      (description "贴片 电阻器")
      (libsource (lib "PCB_CMS_139") (part "R_SMD"))
    )
    (comp (ref "R141")
      (value "10K/1%")
      (footprint "0603R")
      (description "贴片 电阻器")
      (libsource (lib "PCB_CMS_139") (part "R_SMD"))
    )
    (comp (ref "R142")
      (value "510R/1%")
      (footprint "1206R")
      (description "贴片 电阻器")
      (libsource (lib "PCB_CMS_139") (part "R_SMD"))
    )
    (comp (ref "R143")
      (value "1K/1%")
      (footprint "0603R")
      (description "贴片 电阻器")
      (libsource (lib "PCB_CMS_139") (part "R_SMD"))
    )
    (comp (ref "R144")
      (value "510R/1%")
      (footprint "1206R")
      (description "贴片 电阻器")
      (libsource (lib "PCB_CMS_139") (part "R_SMD"))
    )
    (comp (ref "R145")
      (value "5.1K/1%")
      (footprint "0603R")
      (description "贴片 电阻器")
      (libsource (lib "PCB_CMS_139") (part "R_SMD"))
    )
    (comp (ref "R146")
      (value "20R/1%")
      (footprint "1206R")
      (description "贴片 电阻器")
      (libsource (lib "PCB_CMS_139") (part "R_SMD"))
    )
    (comp (ref "R147")
      (value "20R/1%")
      (footprint "1206R")
      (description "贴片 电阻器")
      (libsource (lib "PCB_CMS_139") (part "R_SMD"))
    )
    (comp (ref "R148")
      (value "20R/1%")
      (footprint "1206R")
      (description "贴片 电阻器")
      (libsource (lib "PCB_CMS_139") (part "R_SMD"))
    )
    (comp (ref "R149")
      (value "20R/1%")
      (footprint "1206R")
      (description "贴片 电阻器")
      (libsource (lib "PCB_CMS_139") (part "R_SMD"))
    )
    (comp (ref "R150")
      (value "5.1R 1%")
      (footprint "1206R")
      (description "贴片 电阻器")
      (libsource (lib "PCB_CMS_139") (part "R_SMD"))
    )
    (comp (ref "RP1")
      (value "5.1k/1%")
      (footprint "0603R")
      (description "贴片 电阻器")
      (libsource (lib "PCB_CMS_139") (part "R_SMD"))
    )
    (comp (ref "RP2")
      (value "5.1k/1%")
      (footprint "0603R")
      (description "贴片 电阻器")
      (libsource (lib "PCB_CMS_139") (part "R_SMD"))
    )
    (comp (ref "R_Ddj1")
      (value "200R 1%")
      (footprint "0603R")
      (description "贴片 电阻器")
      (libsource (lib "PCB_CMS_139") (part "R_SMD"))
    )
    (comp (ref "R_Ddj2")
      (value "1.1K 1%")
      (footprint "0603R")
      (description "贴片 电阻器")
      (libsource (lib "PCB_CMS_139") (part "R_SMD"))
    )
    (comp (ref "T1") (value "EF16-7+6") (footprint "EF16-7+7") (libsource (lib "SCH") (part "EF16-7+6")))
    (comp (ref "U1") (value "LV8548MC") (footprint "SOIC-10") (libsource (lib "Schlib1") (part "LV8548MC")))
    (comp (ref "U2")
      (value "1117-5")
      (footprint "SOT-223")
      (description "IC-1117系列稳压块")
      (libsource (lib "PCB_CMS_139") (part "1117"))
    )
    (comp (ref "U3")
      (value "BAT32G139 LQFP48")
      (footprint "mixic_motor_Library_V1.1:LQFP-48")
      (libsource (lib "PCB_CMS_139") (part "CMS32M5333&CMS32M5333L"))
    )
    (comp (ref "U4") (value "LM317") (footprint "TO-252(DPAK)") (libsource (lib "Schlib1") (part "LM317")))
    (comp (ref "U5") (value "UC3845") (footprint "SOIC-8_150mil") (libsource (lib "Schlib1") (part "LM3845")))
    (comp (ref "U6")
      (value "MCP602")
      (footprint "SO-8")
      (description "AMP 0.3V/uS")
      (libsource (lib "motor_sch-2017-6-15") (part "LM358"))
    )
    (comp (ref "U7")
      (value "LM358")
      (footprint "SO-8")
      (description "AMP 0.3V/uS")
      (libsource (lib "motor_sch-2017-6-15") (part "LM358"))
    )
    (comp (ref "U8") (value "LM321") (footprint "SOT23-5") (libsource (lib "Schlib1") (part "LM321")))
    (comp (ref "U10")
      (value "LTV-341P-H")
      (footprint "LSOP6")
      (libsource (lib "2KW nibian PCB_Project-V1.1") (part "LTV-341P-H"))
    )
    (comp (ref "U11")
      (value "LM2903")
      (footprint "SO-8")
      (description "AMP 0.3V/uS")
      (libsource (lib "motor_sch-2017-6-15") (part "LM358"))
    )
    (comp (ref "U12")
      (value "LTV-341P-H")
      (footprint "LSOP6")
      (libsource (lib "2KW nibian PCB_Project-V1.1") (part "LTV-341P-H"))
    )
    (comp (ref "U13")
      (value "LTV-341P-H")
      (footprint "LSOP6")
      (libsource (lib "2KW nibian PCB_Project-V1.1") (part "LTV-341P-H"))
    )
    (comp (ref "U14")
      (value "LTV-341P-H")
      (footprint "LSOP6")
      (libsource (lib "2KW nibian PCB_Project-V1.1") (part "LTV-341P-H"))
    )
    (comp (ref "U15")
      (value "CJ79L05/TO-92")
      (footprint "TO-92 - 7915")
      (libsource (lib "SCH") (part "LM7905"))
    )
    (comp (ref "Y1") (value "8M") (footprint "YY-1") (libsource (lib "SCH") (part "CRYSTAL_1")))
    (comp (ref "Z1")
      (value "15V")
      (footprint "SOD-123")
      (description "贴片 稳压二极管")
      (libsource (lib "PCB_CMS_139") (part "ZD_SMD"))
    )
    (comp (ref "Z2")
      (value "15V")
      (footprint "SOD-123")
      (description "贴片 稳压二极管")
      (libsource (lib "PCB_CMS_139") (part "ZD_SMD"))
    )
    (comp (ref "Z3")
      (value "15V")
      (footprint "SOD-123")
      (description "贴片 稳压二极管")
      (libsource (lib "PCB_CMS_139") (part "ZD_SMD"))
    )
  )
  (nets
    (net (code "1") (name "+5V") (class "Default")
      (node (ref "C23") (pin "2") (pinfunction "2_2") (pintype "passive"))
      (node (ref "C25") (pin "2") (pinfunction "2_2") (pintype "passive"))
      (node (ref "C36") (pin "1") (pinfunction "1_1") (pintype "passive"))
      (node (ref "C46") (pin "1") (pinfunction "1_1") (pintype "passive"))
      (node (ref "C5") (pin "2") (pinfunction "2_2") (pintype "passive"))
      (node (ref "C50") (pin "1") (pinfunction "1_1") (pintype "passive"))
      (node (ref "C7") (pin "2") (pinfunction "2_2") (pintype "passive"))
      (node (ref "C8") (pin "1") (pinfunction "1_1") (pintype "passive"))
      (node (ref "D10") (pin "2") (pinfunction "2_2") (pintype "passive"))
      (node (ref "D13") (pin "2") (pinfunction "2_2") (pintype "passive"))
      (node (ref "D18") (pin "2") (pinfunction "2_2") (pintype "passive"))
      (node (ref "E9") (pin "1") (pinfunction "1_1") (pintype "passive"))
      (node (ref "P3") (pin "1") (pinfunction "1_1") (pintype "passive"))
      (node (ref "Q4") (pin "2") (pinfunction "2_2") (pintype "passive"))
      (node (ref "Q5") (pin "2") (pinfunction "2_2") (pintype "passive"))
      (node (ref "Q6") (pin "2") (pinfunction "2_2") (pintype "passive"))
      (node (ref "Q7") (pin "2") (pinfunction "2_2") (pintype "passive"))
      (node (ref "R110") (pin "1") (pinfunction "1_1") (pintype "passive"))
      (node (ref "R127") (pin "1") (pinfunction "1_1") (pintype "passive"))
      (node (ref "R131") (pin "2") (pinfunction "2_2") (pintype "passive"))
      (node (ref "R136") (pin "2") (pinfunction "2_2") (pintype "passive"))
      (node (ref "R139") (pin "1") (pinfunction "1_1") (pintype "passive"))
      (node (ref "R143") (pin "2") (pinfunction "2_2") (pintype "passive"))
      (node (ref "R26") (pin "1") (pinfunction "1_1") (pintype "passive"))
      (node (ref "R53") (pin "2") (pinfunction "2_2") (pintype "passive"))
      (node (ref "R59") (pin "1") (pinfunction "1_1") (pintype "passive"))
      (node (ref "R67") (pin "1") (pinfunction "1_1") (pintype "passive"))
      (node (ref "R77") (pin "1") (pinfunction "1_1") (pintype "passive"))
      (node (ref "R78") (pin "2") (pinfunction "2_2") (pintype "passive"))
      (node (ref "RP1") (pin "2") (pinfunction "2_2") (pintype "passive"))
      (node (ref "RP2") (pin "1") (pinfunction "1_1") (pintype "passive"))
      (node (ref "U11") (pin "8") (pinfunction "V+_8") (pintype "power_in"))
      (node (ref "U3") (pin "11") (pinfunction "VDD_11") (pintype "passive"))
      (node (ref "U6") (pin "8") (pinfunction "V+_8") (pintype "power_in"))
      (node (ref "U8") (pin "5") (pintype "passive"))
    )
    (net (code "2") (name "+8.5V") (class "Default")
      (node (ref "D5") (pin "K") (pinfunction "K_K") (pintype "passive"))
      (node (ref "E3") (pin "1") (pinfunction "1_1") (pintype "passive"))
      (node (ref "Q15") (pin "3") (pinfunction "C_3") (pintype "passive"))
      (node (ref "R133") (pin "2") (pinfunction "2_2") (pintype "passive"))
      (node (ref "R135") (pin "2") (pinfunction "2_2") (pintype "passive"))
    )
    (net (code "3") (name "+8V") (class "Default")
      (node (ref "C1") (pin "2") (pinfunction "2_2") (pintype "passive"))
      (node (ref "R19") (pin "1") (pinfunction "1_1") (pintype "passive"))
      (node (ref "R_Ddj1") (pin "1") (pinfunction "1_1") (pintype "passive"))
      (node (ref "U1") (pin "1") (pinfunction "VCC_1") (pintype "passive"))
    )
    (net (code "4") (name "+9V") (class "Default")
      (node (ref "C10") (pin "1") (pinfunction "1_1") (pintype "passive"))
      (node (ref "C12") (pin "2") (pinfunction "2_2") (pintype "passive"))
      (node (ref "C17") (pin "1") (pinfunction "1_1") (pintype "passive"))
      (node (ref "C4") (pin "2") (pinfunction "2_2") (pintype "passive"))
      (node (ref "D1") (pin "K") (pinfunction "K_K") (pintype "passive"))
      (node (ref "D8") (pin "A") (pinfunction "A_A") (pintype "passive"))
      (node (ref "E12") (pin "1") (pinfunction "1_1") (pintype "passive"))
      (node (ref "E14") (pin "1") (pinfunction "1_1") (pintype "passive"))
      (node (ref "R22") (pin "1") (pinfunction "1_1") (pintype "passive"))
      (node (ref "R6") (pin "2") (pinfunction "2_2") (pintype "passive"))
      (node (ref "R91") (pin "2") (pinfunction "2_2") (pintype "passive"))
      (node (ref "U4") (pin "3") (pinfunction "Vin_3") (pintype "passive"))
      (node (ref "U7") (pin "8") (pinfunction "V+_8") (pintype "power_in"))
    )
    (net (code "5") (name "+15V-1") (class "Default")
      (node (ref "C80") (pin "1") (pinfunction "1_1") (pintype "passive"))
      (node (ref "C81") (pin "1") (pinfunction "1_1") (pintype "passive"))
      (node (ref "D7") (pin "K") (pinfunction "K_K") (pintype "passive"))
      (node (ref "E10") (pin "1") (pinfunction "1_1") (pintype "passive"))
      (node (ref "R17") (pin "1") (pinfunction "1_1") (pintype "passive"))
      (node (ref "U12") (pin "6") (pinfunction "VCC_6") (pintype "passive"))
      (node (ref "U14") (pin "6") (pinfunction "VCC_6") (pintype "passive"))
      (node (ref "Z3") (pin "K") (pinfunction "2_K") (pintype "passive"))
    )
    (net (code "6") (name "+15V-2") (class "Default")
      (node (ref "C74") (pin "1") (pinfunction "1_1") (pintype "passive"))
      (node (ref "D4") (pin "K") (pinfunction "K_K") (pintype "passive"))
      (node (ref "E5") (pin "1") (pinfunction "1_1") (pintype "passive"))
      (node (ref "R11") (pin "1") (pinfunction "1_1") (pintype "passive"))
      (node (ref "U10") (pin "6") (pinfunction "VCC_6") (pintype "passive"))
      (node (ref "Z2") (pin "K") (pinfunction "2_K") (pintype "passive"))
    )
    (net (code "7") (name "+15V-3") (class "Default")
      (node (ref "C73") (pin "1") (pinfunction "1_1") (pintype "passive"))
      (node (ref "D2") (pin "K") (pinfunction "K_K") (pintype "passive"))
      (node (ref "E1") (pin "1") (pinfunction "1_1") (pintype "passive"))
      (node (ref "R1") (pin "1") (pinfunction "1_1") (pintype "passive"))
      (node (ref "U13") (pin "6") (pinfunction "VCC_6") (pintype "passive"))
      (node (ref "Z1") (pin "K") (pinfunction "2_K") (pintype "passive"))
    )
    (net (code "8") (name "-5V") (class "Default")
      (node (ref "C40") (pin "2") (pinfunction "2_2") (pintype "passive"))
      (node (ref "C44") (pin "1") (pinfunction "1_1") (pintype "passive"))
      (node (ref "R81") (pin "1") (pinfunction "1_1") (pintype "passive"))
      (node (ref "U11") (pin "4") (pinfunction "V-_4") (pintype "power_in"))
      (node (ref "U15") (pin "3") (pinfunction "Vout_3") (pintype "passive"))
    )
    (net (code "9") (name "-5V-1") (class "Default")
      (node (ref "C77") (pin "2") (pinfunction "2_2") (pintype "passive"))
      (node (ref "C78") (pin "2") (pinfunction "2_2") (pintype "passive"))
    )
    (net (code "10") (name "-9V") (class "Default")
      (node (ref "C16") (pin "2") (pinfunction "2_2") (pintype "passive"))
      (node (ref "D26") (pin "A") (pinfunction "A_A") (pintype "passive"))
      (node (ref "E16") (pin "2") (pinfunction "2_2") (pintype "passive"))
      (node (ref "U15") (pin "2") (pinfunction "Vin_2") (pintype "passive"))
    )
    (net (code "11") (name "-9V-1") (class "Default")
      (node (ref "E10") (pin "2") (pinfunction "2_2") (pintype "passive"))
      (node (ref "E11") (pin "2") (pinfunction "2_2") (pintype "passive"))
      (node (ref "R17") (pin "2") (pinfunction "2_2") (pintype "passive"))
      (node (ref "R18") (pin "2") (pinfunction "2_2") (pintype "passive"))
      (node (ref "T1") (pin "8") (pinfunction "8_8") (pintype "passive"))
      (node (ref "U12") (pin "4") (pinfunction "GND_4") (pintype "passive"))
      (node (ref "U14") (pin "4") (pinfunction "GND_4") (pintype "passive"))
    )
    (net (code "12") (name "-9V-2") (class "Default")
      (node (ref "C72") (pin "2") (pinfunction "2_2") (pintype "passive"))
      (node (ref "E5") (pin "2") (pinfunction "2_2") (pintype "passive"))
      (node (ref "E6") (pin "2") (pinfunction "2_2") (pintype "passive"))
      (node (ref "R11") (pin "2") (pinfunction "2_2") (pintype "passive"))
      (node (ref "R12") (pin "2") (pinfunction "2_2") (pintype "passive"))
      (node (ref "T1") (pin "10") (pinfunction "10_10") (pintype "passive"))
      (node (ref "U10") (pin "4") (pinfunction "GND_4") (pintype "passive"))
    )
    (net (code "13") (name "-9V-3") (class "Default")
      (node (ref "C70") (pin "2") (pinfunction "2_2") (pintype "passive"))
      (node (ref "E1") (pin "2") (pinfunction "2_2") (pintype "passive"))
      (node (ref "E2") (pin "2") (pinfunction "2_2") (pintype "passive"))
      (node (ref "R1") (pin "2") (pinfunction "2_2") (pintype "passive"))
      (node (ref "R2") (pin "2") (pinfunction "2_2") (pintype "passive"))
      (node (ref "T1") (pin "12") (pinfunction "12_12") (pintype "passive"))
      (node (ref "U13") (pin "4") (pinfunction "GND_4") (pintype "passive"))
    )
    (net (code "14") (name "/ALARM") (class "Default")
      (node (ref "R145") (pin "2") (pinfunction "2_2") (pintype "passive"))
      (node (ref "RP1") (pin "1") (pinfunction "1_1") (pintype "passive"))
      (node (ref "U3") (pin "14") (pinfunction "P61/SDAA0_14") (pintype "passive"))
    )
    (net (code "15") (name "/DR_UA") (class "Default")
      (node (ref "C58") (pin "1") (pinfunction "1_1") (pintype "passive"))
      (node (ref "Q10") (pin "G") (pinfunction "G_G") (pintype "passive"))
      (node (ref "R102") (pin "1") (pinfunction "1_1") (pintype "passive"))
      (node (ref "R140") (pin "1") (pinfunction "1_1") (pintype "passive"))
    )
    (net (code "16") (name "/DR_UB") (class "Default")
      (node (ref "C59") (pin "1") (pinfunction "1_1") (pintype "passive"))
      (node (ref "Q11") (pin "G") (pinfunction "G_G") (pintype "passive"))
      (node (ref "R103") (pin "1") (pinfunction "1_1") (pintype "passive"))
      (node (ref "R142") (pin "1") (pinfunction "1_1") (pintype "passive"))
    )
    (net (code "17") (name "/DR_UC") (class "Default")
      (node (ref "C60") (pin "1") (pinfunction "1_1") (pintype "passive"))
      (node (ref "Q12") (pin "G") (pinfunction "G_G") (pintype "passive"))
      (node (ref "R104") (pin "1") (pinfunction "1_1") (pintype "passive"))
      (node (ref "R144") (pin "1") (pinfunction "1_1") (pintype "passive"))
    )
    (net (code "18") (name "/Ddj") (class "Default")
      (node (ref "R_Ddj1") (pin "2") (pinfunction "2_2") (pintype "passive"))
      (node (ref "R_Ddj2") (pin "1") (pinfunction "1_1") (pintype "passive"))
      (node (ref "U4") (pin "1") (pinfunction "Ddj_1") (pintype "passive"))
    )
    (net (code "19") (name "/ECO") (class "Default")
      (node (ref "C79") (pin "2") (pinfunction "2_2") (pintype "passive"))
      (node (ref "D18") (pin "3") (pinfunction "3_3") (pintype "passive"))
      (node (ref "R127") (pin "2") (pinfunction "2_2") (pintype "passive"))
      (node (ref "R128") (pin "1") (pinfunction "1_1") (pintype "passive"))
      (node (ref "U3") (pin "19") (pinfunction "P74/INPT8_19") (pintype "passive"))
    )
    (net (code "20") (name "/EN_DR") (class "Default")
      (node (ref "PQ2") (pin "1") (pinfunction "1_1") (pintype "passive"))
      (node (ref "Q2") (pin "3") (pinfunction "C_3") (pintype "passive"))
      (node (ref "R35") (pin "1") (pinfunction "1_1") (pintype "passive"))
      (node (ref "R50") (pin "2") (pinfunction "2_2") (pintype "passive"))
    )
    (net (code "21") (name "/EN_REC") (class "Default")
      (node (ref "R49") (pin "2") (pinfunction "2_2") (pintype "passive"))
      (node (ref "U3") (pin "24") (pinfunction "P30/INTP3/TAO/(TMIOB1)_24") (pintype "passive"))
    )
    (net (code "22") (name "/FRQ_WAVE") (class "Default")
      (node (ref "C53") (pin "2") (pinfunction "2_2") (pintype "passive"))
      (node (ref "R85") (pin "2") (pinfunction "2_2") (pintype "passive"))
      (node (ref "U3") (pin "42") (pinfunction "P22/ANI2PGA0IN/VCIN0_42") (pintype "passive"))
    )
    (net (code "23") (name "/GREEN") (class "Default")
      (node (ref "P13") (pin "4") (pinfunction "4_4") (pintype "passive"))
      (node (ref "Q18") (pin "2") (pinfunction "E_2") (pintype "passive"))
    )
    (net (code "24") (name "/IL") (class "Default")
      (node (ref "L2") (pin "1") (pinfunction "1_1") (pintype "passive"))
      (node (ref "P11") (pin "1") (pinfunction "1_1") (pintype "passive"))
      (node (ref "R122") (pin "1") (pinfunction "1_1") (pintype "passive"))
      (node (ref "R65") (pin "1") (pinfunction "1_1") (pintype "passive"))
      (node (ref "R74") (pin "2") (pinfunction "2_2") (pintype "passive"))
    )
    (net (code "25") (name "/IL_AD") (class "Default")
      (node (ref "C37") (pin "2") (pinfunction "2_2") (pintype "passive"))
      (node (ref "Q6") (pin "3") (pinfunction "3_3") (pintype "passive"))
      (node (ref "R63") (pin "2") (pinfunction "2_2") (pintype "passive"))
      (node (ref "U3") (pin "35") (pinfunction "P146/ANI15_35") (pintype "passive"))
    )
    (net (code "26") (name "/I_LIMIT") (class "Default")
      (node (ref "C51") (pin "2") (pinfunction "2_2") (pintype "passive"))
      (node (ref "D27") (pin "K") (pinfunction "K_K") (pintype "passive"))
      (node (ref "R78") (pin "1") (pinfunction "1_1") (pintype "passive"))
      (node (ref "R80") (pin "2") (pinfunction "2_2") (pintype "passive"))
      (node (ref "U3") (pin "12") (pinfunction "P136/INPT0_12") (pintype "passive"))
    )
    (net (code "27") (name "/KEY-ECO") (class "Default")
      (node (ref "D19") (pin "K") (pinfunction "K_K") (pintype "passive"))
      (node (ref "P13") (pin "6") (pinfunction "6_6") (pintype "passive"))
    )
    (net (code "28") (name "/KEY-P_CUT") (class "Default")
      (node (ref "D14") (pin "K") (pinfunction "K_K") (pintype "passive"))
      (node (ref "P13") (pin "5") (pinfunction "5_5") (pintype "passive"))
    )
    (net (code "29") (name "/LINE_L") (class "Default")
      (node (ref "C69") (pin "2") (pinfunction "2_2") (pintype "passive"))
      (node (ref "CY1") (pin "2") (pinfunction "2_2") (pintype "passive"))
      (node (ref "L1") (pin "2") (pinfunction "2_2") (pintype "passive"))
      (node (ref "P7") (pin "1") (pinfunction "1_1") (pintype "passive"))
      (node (ref "P8") (pin "1") (pinfunction "1_1") (pintype "passive"))
      (node (ref "R38") (pin "1") (pinfunction "1_1") (pintype "passive"))
    )
    (net (code "30") (name "/NORMAL") (class "Default")
      (node (ref "R132") (pin "1") (pinfunction "1_1") (pintype "passive"))
      (node (ref "RP2") (pin "2") (pinfunction "2_2") (pintype "passive"))
      (node (ref "U3") (pin "13") (pinfunction "P60/SCLA0_13") (pintype "passive"))
    )
    (net (code "31") (name "/NTC_AD") (class "Default")
      (node (ref "C49") (pin "2") (pinfunction "2_2") (pintype "passive"))
      (node (ref "P14") (pin "2") (pinfunction "2_2") (pintype "passive"))
      (node (ref "Q7") (pin "3") (pinfunction "3_3") (pintype "passive"))
      (node (ref "R77") (pin "2") (pinfunction "2_2") (pintype "passive"))
      (node (ref "U3") (pin "44") (pinfunction "P20/ANI0/AVREFP/VCIN12_44") (pintype "passive"))
    )
    (net (code "32") (name "/OSC1") (class "Default")
      (node (ref "C41") (pin "2") (pinfunction "2_2") (pintype "passive"))
      (node (ref "R64") (pin "2") (pinfunction "2_2") (pintype "passive"))
      (node (ref "U3") (pin "9") (pinfunction "P121/X1_9") (pintype "passive"))
      (node (ref "Y1") (pin "3") (pinfunction "3_3") (pintype "passive"))
    )
    (net (code "33") (name "/OSC2") (class "Default")
      (node (ref "C34") (pin "2") (pinfunction "2_2") (pintype "passive"))
      (node (ref "R64") (pin "1") (pinfunction "1_1") (pintype "passive"))
      (node (ref "U3") (pin "8") (pinfunction "P122/X2_8") (pintype "passive"))
      (node (ref "Y1") (pin "1") (pinfunction "1_1") (pintype "passive"))
    )
    (net (code "34") (name "/PWM1H") (class "Default")
      (node (ref "R68") (pin "1") (pinfunction "1_1") (pintype "passive"))
      (node (ref "U3") (pin "32") (pinfunction "P12/TMIOA1_32") (pintype "passive"))
    )
    (net (code "35") (name "/PWM1L") (class "Default")
      (node (ref "R75") (pin "1") (pinfunction "1_1") (pintype "passive"))
      (node (ref "U3") (pin "31") (pinfunction "P13/TXD2/TMIOC1_31") (pintype "passive"))
    )
    (net (code "36") (name "/PWM2H") (class "Default")
      (node (ref "R82") (pin "1") (pinfunction "1_1") (pintype "passive"))
      (node (ref "U3") (pin "30") (pinfunction "P14/RXD2/TMIOB0_30") (pintype "passive"))
    )
    (net (code "37") (name "/PWM2L") (class "Default")
      (node (ref "R87") (pin "1") (pinfunction "1_1") (pintype "passive"))
      (node (ref "U3") (pin "29") (pinfunction "P15/TMIOD0_29") (pintype "passive"))
    )
    (net (code "38") (name "/P_CUT") (class "Default")
      (node (ref "C71") (pin "2") (pinfunction "2_2") (pintype "passive"))
      (node (ref "D13") (pin "3") (pinfunction "3_3") (pintype "passive"))
      (node (ref "R110") (pin "2") (pinfunction "2_2") (pintype "passive"))
      (node (ref "R111") (pin "1") (pinfunction "1_1") (pintype "passive"))
      (node (ref "U3") (pin "17") (pinfunction "P31/VCOUT1/INTP4/TI03/TO03_17") (pintype "passive"))
    )
    (net (code "39") (name "/RED") (class "Default")
      (node (ref "P13") (pin "2") (pinfunction "2_2") (pintype "passive"))
      (node (ref "Q19") (pin "2") (pinfunction "E_2") (pintype "passive"))
    )
    (net (code "40") (name "/RESET") (class "Default")
      (node (ref "C33") (pin "2") (pinfunction "2_2") (pintype "passive"))
      (node (ref "P3") (pin "3") (pinfunction "3_3") (pintype "passive"))
      (node (ref "R59") (pin "2") (pinfunction "2_2") (pintype "passive"))
      (node (ref "U3") (pin "4") (pinfunction "RESETB_4") (pintype "passive"))
    )
    (net (code "41") (name "/SPEED") (class "Default")
      (node (ref "C82") (pin "2") (pinfunction "2_2") (pintype "passive"))
      (node (ref "R137") (pin "1") (pinfunction "1_1") (pintype "passive"))
      (node (ref "U3") (pin "25") (pinfunction "P50/INTP1/RXD0/TBIO0/(TMIOC1)_25") (pintype "passive"))
    )
    (net (code "42") (name "/STEP_A") (class "Default")
      (node (ref "R3") (pin "1") (pinfunction "1_1") (pintype "passive"))
      (node (ref "U3") (pin "40") (pinfunction "P24/ANI4/PGA1IN_40") (pintype "passive"))
    )
    (net (code "43") (name "/STEP_B") (class "Default")
      (node (ref "R4") (pin "1") (pinfunction "1_1") (pintype "passive"))
      (node (ref "U3") (pin "38") (pinfunction "P26/ANI6_38") (pintype "passive"))
    )
    (net (code "44") (name "/STEP_C") (class "Default")
      (node (ref "R5") (pin "1") (pinfunction "1_1") (pintype "passive"))
      (node (ref "U3") (pin "37") (pinfunction "P27/ANI17_37") (pintype "passive"))
    )
    (net (code "45") (name "/STEP_D") (class "Default")
      (node (ref "R7") (pin "1") (pinfunction "1_1") (pintype "passive"))
      (node (ref "U3") (pin "39") (pinfunction "P25/ANI5/PGA1GND_39") (pintype "passive"))
    )
    (net (code "46") (name "/SWCLK") (class "Default")
      (node (ref "P3") (pin "5") (pinfunction "5_5") (pintype "passive"))
      (node (ref "U3") (pin "7") (pinfunction "P137/SWCLK_7") (pintype "passive"))
    )
    (net (code "47") (name "/SWDIO") (class "Default")
      (node (ref "P3") (pin "4") (pinfunction "4_4") (pintype "passive"))
      (node (ref "U3") (pin "3") (pinfunction "P40/SWDIO_3") (pintype "passive"))
    )
    (net (code "48") (name "/TX") (class "Default")
      (node (ref "R86") (pin "2") (pinfunction "2_2") (pintype "passive"))
      (node (ref "U3") (pin "21") (pinfunction "P72/(TXD1)_21") (pintype "passive"))
    )
    (net (code "49") (name "/UA") (class "Default")
      (node (ref "C62") (pin "1") (pinfunction "1_1") (pintype "passive"))
      (node (ref "C66") (pin "2") (pinfunction "2_2") (pintype "passive"))
      (node (ref "D15") (pin "2") (pinfunction "2_2") (pintype "passive"))
      (node (ref "P4") (pin "1") (pinfunction "1_1") (pintype "passive"))
      (node (ref "Q10") (pin "A") (pinfunction "A_A") (pintype "passive"))
    )
    (net (code "50") (name "/UB") (class "Default")
      (node (ref "C63") (pin "1") (pinfunction "1_1") (pintype "passive"))
      (node (ref "C67") (pin "2") (pinfunction "2_2") (pintype "passive"))
      (node (ref "D16") (pin "2") (pinfunction "2_2") (pintype "passive"))
      (node (ref "P4") (pin "3") (pinfunction "3_3") (pintype "passive"))
      (node (ref "Q11") (pin "A") (pinfunction "A_A") (pintype "passive"))
    )
    (net (code "51") (name "/UBUS_AD") (class "Default")
      (node (ref "C28") (pin "2") (pinfunction "2_2") (pintype "passive"))
      (node (ref "Q5") (pin "3") (pinfunction "3_3") (pintype "passive"))
      (node (ref "R54") (pin "2") (pinfunction "2_2") (pintype "passive"))
      (node (ref "U3") (pin "46") (pinfunction "P01/ANI10RXD1/VCIN11/TAIO_46") (pintype "passive"))
    )
    (net (code "52") (name "/UC") (class "Default")
      (node (ref "C64") (pin "1") (pinfunction "1_1") (pintype "passive"))
      (node (ref "C68") (pin "2") (pinfunction "2_2") (pintype "passive"))
      (node (ref "D17") (pin "2") (pinfunction "2_2") (pintype "passive"))
      (node (ref "P4") (pin "2") (pinfunction "2_2") (pintype "passive"))
      (node (ref "Q12") (pin "A") (pinfunction "A_A") (pintype "passive"))
    )
    (net (code "53") (name "/VAC") (class "Default")
      (node (ref "C26") (pin "1") (pinfunction "1_1") (pintype "passive"))
      (node (ref "C27") (pin "1") (pinfunction "1_1") (pintype "passive"))
      (node (ref "R42") (pin "1") (pinfunction "1_1") (pintype "passive"))
      (node (ref "R52") (pin "2") (pinfunction "2_2") (pintype "passive"))
      (node (ref "R85") (pin "1") (pinfunction "1_1") (pintype "passive"))
      (node (ref "U6") (pin "7") (pinfunction "OUT_7") (pintype "output"))
    )
    (net (code "54") (name "/VAC_AD") (class "Default")
      (node (ref "C24") (pin "2") (pinfunction "2_2") (pintype "passive"))
      (node (ref "Q4") (pin "3") (pinfunction "3_3") (pintype "passive"))
      (node (ref "R42") (pin "2") (pinfunction "2_2") (pintype "passive"))
      (node (ref "U3") (pin "41") (pinfunction "P23/ANI3PGA0GND_41") (pintype "passive"))
    )
    (net (code "55") (name "/VCC_AD") (class "Default")
      (node (ref "C54") (pin "2") (pinfunction "2_2") (pintype "passive"))
      (node (ref "D10") (pin "3") (pinfunction "3_3") (pintype "passive"))
      (node (ref "R90") (pin "2") (pinfunction "2_2") (pintype "passive"))
      (node (ref "U3") (pin "47") (pinfunction "P00/ANI11/TXD1/VCIN10TI00_47") (pintype "passive"))
    )
    (net (code "56") (name "/VO1") (class "Default")
      (node (ref "R108") (pin "1") (pinfunction "1_1") (pintype "passive"))
      (node (ref "R146") (pin "1") (pinfunction "1_1") (pintype "passive"))
      (node (ref "U10") (pin "5") (pinfunction "VO_5") (pintype "passive"))
    )
    (net (code "57") (name "/VO2") (class "Default")
      (node (ref "R123") (pin "1") (pinfunction "1_1") (pintype "passive"))
      (node (ref "R148") (pin "1") (pinfunction "1_1") (pintype "passive"))
      (node (ref "U12") (pin "5") (pinfunction "VO_5") (pintype "passive"))
    )
    (net (code "58") (name "/VO3") (class "Default")
      (node (ref "R109") (pin "1") (pinfunction "1_1") (pintype "passive"))
      (node (ref "R147") (pin "1") (pinfunction "1_1") (pintype "passive"))
      (node (ref "U13") (pin "5") (pinfunction "VO_5") (pintype "passive"))
    )
    (net (code "59") (name "/VO4") (class "Default")
      (node (ref "R124") (pin "1") (pinfunction "1_1") (pintype "passive"))
      (node (ref "R149") (pin "1") (pinfunction "1_1") (pintype "passive"))
      (node (ref "U14") (pin "5") (pinfunction "VO_5") (pintype "passive"))
    )
    (net (code "60") (name "/VREF_AD") (class "Default")
      (node (ref "C55") (pin "2") (pinfunction "2_2") (pintype "passive"))
      (node (ref "R92") (pin "2") (pinfunction "2_2") (pintype "passive"))
      (node (ref "U3") (pin "34") (pinfunction "P10TMIOB1/ANI9_34") (pintype "passive"))
    )
    (net (code "61") (name "10VAC+") (class "Default")
      (node (ref "C2") (pin "2") (pinfunction "2_2") (pintype "passive"))
      (node (ref "D3") (pin "A") (pinfunction "A_A") (pintype "passive"))
      (node (ref "D6") (pin "K") (pinfunction "K_K") (pintype "passive"))
      (node (ref "P2") (pin "2") (pinfunction "2_2") (pintype "passive"))
      (node (ref "R134") (pin "1") (pinfunction "1_1") (pintype "passive"))
    )
    (net (code "62") (name "10VAC-") (class "Default")
      (node (ref "C2") (pin "1") (pinfunction "1_1") (pintype "passive"))
      (node (ref "C83") (pin "1") (pinfunction "1_1") (pintype "passive"))
      (node (ref "D21") (pin "A") (pinfunction "A_A") (pintype "passive"))
      (node (ref "E4") (pin "2") (pinfunction "2_2") (pintype "passive"))
      (node (ref "E8") (pin "1") (pinfunction "1_1") (pintype "passive"))
      (node (ref "P2") (pin "1") (pinfunction "1_1") (pintype "passive"))
      (node (ref "PQ1") (pin "2") (pinfunction "2_2") (pintype "passive"))
      (node (ref "R13") (pin "1") (pinfunction "1_1") (pintype "passive"))
      (node (ref "R8") (pin "2") (pinfunction "2_2") (pintype "passive"))
    )
    (net (code "63") (name "AGND") (class "Default")
      (node (ref "C1") (pin "1") (pinfunction "1_1") (pintype "passive"))
      (node (ref "C10") (pin "2") (pinfunction "2_2") (pintype "passive"))
      (node (ref "C11") (pin "2") (pinfunction "2_2") (pintype "passive"))
      (node (ref "C12") (pin "1") (pinfunction "1_1") (pintype "passive"))
      (node (ref "C15") (pin "2") (pinfunction "2_2") (pintype "passive"))
      (node (ref "C16") (pin "1") (pinfunction "1_1") (pintype "passive"))
      (node (ref "C17") (pin "2") (pinfunction "2_2") (pintype "passive"))
      (node (ref "C18") (pin "2") (pinfunction "2_2") (pintype "passive"))
      (node (ref "C19") (pin "1") (pinfunction "1_1") (pintype "passive"))
      (node (ref "C20") (pin "2") (pinfunction "2_2") (pintype "passive"))
      (node (ref "C22") (pin "2") (pinfunction "2_2") (pintype "passive"))
      (node (ref "C23") (pin "1") (pinfunction "1_1") (pintype "passive"))
      (node (ref "C24") (pin "1") (pinfunction "1_1") (pintype "passive"))
      (node (ref "C28") (pin "1") (pinfunction "1_1") (pintype "passive"))
      (node (ref "C30") (pin "2") (pinfunction "2_2") (pintype "passive"))
      (node (ref "C32") (pin "1") (pinfunction "1_1") (pintype "passive"))
      (node (ref "C33") (pin "1") (pinfunction "1_1") (pintype "passive"))
      (node (ref "C34") (pin "1") (pinfunction "1_1") (pintype "passive"))
      (node (ref "C36") (pin "2") (pinfunction "2_2") (pintype "passive"))
      (node (ref "C37") (pin "1") (pinfunction "1_1") (pintype "passive"))
      (node (ref "C4") (pin "1") (pinfunction "1_1") (pintype "passive"))
      (node (ref "C40") (pin "1") (pinfunction "1_1") (pintype "passive"))
      (node (ref "C41") (pin "1") (pinfunction "1_1") (pintype "passive"))
      (node (ref "C42") (pin "1") (pinfunction "1_1") (pintype "passive"))
      (node (ref "C44") (pin "2") (pinfunction "2_2") (pintype "passive"))
      (node (ref "C45") (pin "1") (pinfunction "1_1") (pintype "passive"))
      (node (ref "C46") (pin "2") (pinfunction "2_2") (pintype "passive"))
      (node (ref "C47") (pin "2") (pinfunction "2_2") (pintype "passive"))
      (node (ref "C49") (pin "1") (pinfunction "1_1") (pintype "passive"))
      (node (ref "C5") (pin "1") (pinfunction "1_1") (pintype "passive"))
      (node (ref "C50") (pin "2") (pinfunction "2_2") (pintype "passive"))
      (node (ref "C51") (pin "1") (pinfunction "1_1") (pintype "passive"))
      (node (ref "C53") (pin "1") (pinfunction "1_1") (pintype "passive"))
      (node (ref "C54") (pin "1") (pinfunction "1_1") (pintype "passive"))
      (node (ref "C55") (pin "1") (pinfunction "1_1") (pintype "passive"))
      (node (ref "C6") (pin "1") (pinfunction "1_1") (pintype "passive"))
      (node (ref "C69") (pin "1") (pinfunction "1_1") (pintype "passive"))
      (node (ref "C7") (pin "1") (pinfunction "1_1") (pintype "passive"))
      (node (ref "C71") (pin "1") (pinfunction "1_1") (pintype "passive"))
      (node (ref "C79") (pin "1") (pinfunction "1_1") (pintype "passive"))
      (node (ref "C8") (pin "2") (pinfunction "2_2") (pintype "passive"))
      (node (ref "C82") (pin "1") (pinfunction "1_1") (pintype "passive"))
      (node (ref "CY2") (pin "1") (pinfunction "1_1") (pintype "passive"))
      (node (ref "D10") (pin "1") (pinfunction "1_1") (pintype "passive"))
      (node (ref "D13") (pin "1") (pinfunction "1_1") (pintype "passive"))
      (node (ref "D18") (pin "1") (pinfunction "1_1") (pintype "passive"))
      (node (ref "D27") (pin "A") (pinfunction "A_A") (pintype "passive"))
      (node (ref "D6") (pin "A") (pinfunction "A_A") (pintype "passive"))
      (node (ref "E12") (pin "2") (pinfunction "2_2") (pintype "passive"))
      (node (ref "E13") (pin "2") (pinfunction "2_2") (pintype "passive"))
      (node (ref "E14") (pin "2") (pinfunction "2_2") (pintype "passive"))
      (node (ref "E16") (pin "1") (pinfunction "1_1") (pintype "passive"))
      (node (ref "E8") (pin "2") (pinfunction "2_2") (pintype "passive"))
      (node (ref "E9") (pin "2") (pinfunction "2_2") (pintype "passive"))
      (node (ref "P12") (pin "1") (pinfunction "1_1") (pintype "passive"))
      (node (ref "P13") (pin "1") (pinfunction "1_1") (pintype "passive"))
      (node (ref "P14") (pin "1") (pinfunction "1_1") (pintype "passive"))
      (node (ref "P3") (pin "2") (pinfunction "2_2") (pintype "passive"))
      (node (ref "P5") (pin "2") (pinfunction "2_2") (pintype "passive"))
      (node (ref "PQ2") (pin "2") (pinfunction "2_2") (pintype "passive"))
      (node (ref "Q17") (pin "2") (pinfunction "E_2") (pintype "passive"))
      (node (ref "Q2") (pin "2") (pinfunction "E_2") (pintype "passive"))
      (node (ref "Q3") (pin "2") (pinfunction "E_2") (pintype "passive"))
      (node (ref "Q4") (pin "1") (pinfunction "1_1") (pintype "passive"))
      (node (ref "Q5") (pin "1") (pinfunction "1_1") (pintype "passive"))
      (node (ref "Q6") (pin "1") (pinfunction "1_1") (pintype "passive"))
      (node (ref "Q7") (pin "1") (pinfunction "1_1") (pintype "passive"))
      (node (ref "R122") (pin "2") (pinfunction "2_2") (pintype "passive"))
      (node (ref "R13") (pin "2") (pinfunction "2_2") (pintype "passive"))
      (node (ref "R141") (pin "1") (pinfunction "1_1") (pintype "passive"))
      (node (ref "R23") (pin "2") (pinfunction "2_2") (pintype "passive"))
      (node (ref "R24") (pin "2") (pinfunction "2_2") (pintype "passive"))
      (node (ref "R31") (pin "2") (pinfunction "2_2") (pintype "passive"))
      (node (ref "R32") (pin "2") (pinfunction "2_2") (pintype "passive"))
      (node (ref "R33") (pin "1") (pinfunction "1_1") (pintype "passive"))
      (node (ref "R36") (pin "2") (pinfunction "2_2") (pintype "passive"))
      (node (ref "R44") (pin "1") (pinfunction "1_1") (pintype "passive"))
      (node (ref "R50") (pin "1") (pinfunction "1_1") (pintype "passive"))
      (node (ref "R55") (pin "1") (pinfunction "1_1") (pintype "passive"))
      (node (ref "R57") (pin "2") (pinfunction "2_2") (pintype "passive"))
      (node (ref "R58") (pin "1") (pinfunction "1_1") (pintype "passive"))
      (node (ref "R62") (pin "2") (pinfunction "2_2") (pintype "passive"))
      (node (ref "R70") (pin "1") (pinfunction "1_1") (pintype "passive"))
      (node (ref "R71") (pin "1") (pinfunction "1_1") (pintype "passive"))
      (node (ref "R76") (pin "1") (pinfunction "1_1") (pintype "passive"))
      (node (ref "R79") (pin "2") (pinfunction "2_2") (pintype "passive"))
      (node (ref "R83") (pin "1") (pinfunction "1_1") (pintype "passive"))
      (node (ref "R88") (pin "1") (pinfunction "1_1") (pintype "passive"))
      (node (ref "R89") (pin "2") (pinfunction "2_2") (pintype "passive"))
      (node (ref "R_Ddj2") (pin "2") (pinfunction "2_2") (pintype "passive"))
      (node (ref "T1") (pin "4") (pinfunction "4_4") (pintype "passive"))
      (node (ref "U1") (pin "6") (pinfunction "GND_6") (pintype "passive"))
      (node (ref "U10") (pin "3") (pinfunction "VF-_3") (pintype "passive"))
      (node (ref "U12") (pin "3") (pinfunction "VF-_3") (pintype "passive"))
      (node (ref "U13") (pin "3") (pinfunction "VF-_3") (pintype "passive"))
      (node (ref "U14") (pin "3") (pinfunction "VF-_3") (pintype "passive"))
      (node (ref "U15") (pin "1") (pinfunction "GND_1") (pintype "passive"))
      (node (ref "U2") (pin "1") (pintype "passive"))
      (node (ref "U3") (pin "10") (pinfunction "VSS_10") (pintype "passive"))
      (node (ref "U5") (pin "5") (pinfunction "GND_5") (pintype "passive"))
      (node (ref "U6") (pin "4") (pinfunction "V-_4") (pintype "power_in"))
      (node (ref "U7") (pin "4") (pinfunction "V-_4") (pintype "power_in"))
      (node (ref "U8") (pin "2") (pintype "passive"))
      (node (ref "Y1") (pin "2") (pinfunction "2_2") (pintype "passive"))
      (node (ref "Y1") (pin "4") (pinfunction "4_4") (pintype "passive"))
    )
    (net (code "64") (name "GND-1") (class "Default")
      (node (ref "C57") (pin "1") (pinfunction "1_1") (pintype "passive"))
      (node (ref "C77") (pin "1") (pinfunction "1_1") (pintype "passive"))
      (node (ref "C78") (pin "1") (pinfunction "1_1") (pintype "passive"))
      (node (ref "C80") (pin "2") (pinfunction "2_2") (pintype "passive"))
      (node (ref "C81") (pin "2") (pinfunction "2_2") (pintype "passive"))
      (node (ref "D15") (pin "1") (pinfunction "1_1") (pintype "passive"))
      (node (ref "D16") (pin "1") (pinfunction "1_1") (pintype "passive"))
      (node (ref "D17") (pin "1") (pinfunction "1_1") (pintype "passive"))
      (node (ref "E11") (pin "1") (pinfunction "1_1") (pintype "passive"))
      (node (ref "E15") (pin "2") (pinfunction "2_2") (pintype "passive"))
      (node (ref "Q13") (pin "S") (pinfunction "S_S") (pintype "input"))
      (node (ref "Q14") (pin "S") (pinfunction "S_S") (pintype "input"))
      (node (ref "R115") (pin "1") (pinfunction "1_1") (pintype "passive"))
      (node (ref "R116") (pin "1") (pinfunction "1_1") (pintype "passive"))
      (node (ref "R117") (pin "1") (pinfunction "1_1") (pintype "passive"))
      (node (ref "R118") (pin "1") (pinfunction "1_1") (pintype "passive"))
      (node (ref "R119") (pin "2") (pinfunction "2_2") (pintype "passive"))
      (node (ref "R125") (pin "2") (pinfunction "2_2") (pintype "passive"))
      (node (ref "R126") (pin "1") (pinfunction "1_1") (pintype "passive"))
      (node (ref "R129") (pin "1") (pinfunction "1_1") (pintype "passive"))
      (node (ref "R130") (pin "1") (pinfunction "1_1") (pintype "passive"))
      (node (ref "R18") (pin "1") (pinfunction "1_1") (pintype "passive"))
      (node (ref "Z3") (pin "A") (pinfunction "1_A") (pintype "passive"))
    )
    (net (code "65") (name "GND-2") (class "Default")
      (node (ref "C61") (pin "1") (pinfunction "1_1") (pintype "passive"))
      (node (ref "C72") (pin "1") (pinfunction "1_1") (pintype "passive"))
      (node (ref "C74") (pin "2") (pinfunction "2_2") (pintype "passive"))
      (node (ref "C76") (pin "2") (pinfunction "2_2") (pintype "passive"))
      (node (ref "E6") (pin "1") (pinfunction "1_1") (pintype "passive"))
      (node (ref "L1") (pin "1") (pinfunction "1_1") (pintype "passive"))
      (node (ref "P6") (pin "1") (pinfunction "1_1") (pintype "passive"))
      (node (ref "Q13") (pin "D") (pinfunction "D_D") (pintype "input"))
      (node (ref "Q8") (pin "S") (pinfunction "S_S") (pintype "input"))
      (node (ref "R113") (pin "1") (pinfunction "1_1") (pintype "passive"))
      (node (ref "R12") (pin "1") (pinfunction "1_1") (pintype "passive"))
      (node (ref "Z2") (pin "A") (pinfunction "1_A") (pintype "passive"))
    )
    (net (code "66") (name "GND-3") (class "Default")
      (node (ref "C65") (pin "1") (pinfunction "1_1") (pintype "passive"))
      (node (ref "C70") (pin "1") (pinfunction "1_1") (pintype "passive"))
      (node (ref "C73") (pin "2") (pinfunction "2_2") (pintype "passive"))
      (node (ref "C75") (pin "1") (pinfunction "1_1") (pintype "passive"))
      (node (ref "E2") (pin "1") (pinfunction "1_1") (pintype "passive"))
      (node (ref "L2") (pin "2") (pinfunction "2_2") (pintype "passive"))
      (node (ref "P10") (pin "1") (pinfunction "1_1") (pintype "passive"))
      (node (ref "Q14") (pin "D") (pinfunction "D_D") (pintype "input"))
      (node (ref "Q9") (pin "S") (pinfunction "S_S") (pintype "input"))
      (node (ref "R114") (pin "1") (pinfunction "1_1") (pintype "passive"))
      (node (ref "R2") (pin "1") (pinfunction "1_1") (pintype "passive"))
      (node (ref "Z1") (pin "A") (pinfunction "1_A") (pintype "passive"))
    )
    (net (code "67") (name "Net-(C3-Pad1)") (class "Default")
      (node (ref "C3") (pin "1") (pinfunction "1_1") (pintype "passive"))
      (node (ref "D3") (pin "K") (pinfunction "K_K") (pintype "passive"))
      (node (ref "E4") (pin "1") (pinfunction "1_1") (pintype "passive"))
      (node (ref "R10") (pin "2") (pinfunction "2_2") (pintype "passive"))
      (node (ref "R8") (pin "1") (pinfunction "1_1") (pintype "passive"))
      (node (ref "R9") (pin "2") (pinfunction "2_2") (pintype "passive"))
      (node (ref "T1") (pin "1") (pinfunction "1_1") (pintype "passive"))
    )
    (net (code "68") (name "Net-(C3-Pad2)") (class "Default")
      (node (ref "C3") (pin "2") (pinfunction "2_2") (pintype "passive"))
      (node (ref "D9") (pin "K") (pinfunction "K_K") (pintype "passive"))
      (node (ref "R14") (pin "1") (pinfunction "1_1") (pintype "passive"))
    )
    (net (code "69") (name "Net-(C14-Pad2)") (class "Default")
      (node (ref "C14") (pin "2") (pinfunction "2_2") (pintype "passive"))
      (node (ref "R28") (pin "2") (pinfunction "2_2") (pintype "passive"))
      (node (ref "R29") (pin "2") (pinfunction "2_2") (pintype "passive"))
    )
    (net (code "70") (name "Net-(C27-Pad2)") (class "Default")
      (node (ref "C27") (pin "2") (pinfunction "2_2") (pintype "passive"))
      (node (ref "R51") (pin "2") (pinfunction "2_2") (pintype "passive"))
      (node (ref "R52") (pin "1") (pinfunction "1_1") (pintype "passive"))
    )
    (net (code "71") (name "Net-(C30-Pad1)") (class "Default")
      (node (ref "C30") (pin "1") (pinfunction "1_1") (pintype "passive"))
      (node (ref "R53") (pin "1") (pinfunction "1_1") (pintype "passive"))
      (node (ref "R58") (pin "2") (pinfunction "2_2") (pintype "passive"))
      (node (ref "U8") (pin "1") (pintype "passive"))
    )
    (net (code "72") (name "Net-(C61-Pad2)") (class "Default")
      (node (ref "C61") (pin "2") (pinfunction "2_2") (pintype "passive"))
      (node (ref "R105") (pin "1") (pinfunction "1_1") (pintype "passive"))
    )
    (net (code "73") (name "Net-(C62-Pad2)") (class "Default")
      (node (ref "C62") (pin "2") (pinfunction "2_2") (pintype "passive"))
      (node (ref "R99") (pin "1") (pinfunction "1_1") (pintype "passive"))
    )
    (net (code "74") (name "Net-(C63-Pad2)") (class "Default")
      (node (ref "C63") (pin "2") (pinfunction "2_2") (pintype "passive"))
      (node (ref "R100") (pin "1") (pinfunction "1_1") (pintype "passive"))
    )
    (net (code "75") (name "Net-(C64-Pad2)") (class "Default")
      (node (ref "C64") (pin "2") (pinfunction "2_2") (pintype "passive"))
      (node (ref "R101") (pin "1") (pinfunction "1_1") (pintype "passive"))
    )
    (net (code "76") (name "Net-(C65-Pad2)") (class "Default")
      (node (ref "C65") (pin "2") (pinfunction "2_2") (pintype "passive"))
      (node (ref "R106") (pin "1") (pinfunction "1_1") (pintype "passive"))
    )
    (net (code "77") (name "Net-(C66-Pad1)") (class "Default")
      (node (ref "C66") (pin "1") (pinfunction "1_1") (pintype "passive"))
      (node (ref "R116") (pin "2") (pinfunction "2_2") (pintype "passive"))
    )
    (net (code "78") (name "Net-(C67-Pad1)") (class "Default")
      (node (ref "C67") (pin "1") (pinfunction "1_1") (pintype "passive"))
      (node (ref "R117") (pin "2") (pinfunction "2_2") (pintype "passive"))
    )
    (net (code "79") (name "Net-(C68-Pad1)") (class "Default")
      (node (ref "C68") (pin "1") (pinfunction "1_1") (pintype "passive"))
      (node (ref "R118") (pin "2") (pinfunction "2_2") (pintype "passive"))
    )
    (net (code "80") (name "Net-(C75-Pad2)") (class "Default")
      (node (ref "C75") (pin "2") (pinfunction "2_2") (pintype "passive"))
      (node (ref "R125") (pin "1") (pinfunction "1_1") (pintype "passive"))
    )
    (net (code "81") (name "Net-(C76-Pad1)") (class "Default")
      (node (ref "C76") (pin "1") (pinfunction "1_1") (pintype "passive"))
      (node (ref "R126") (pin "2") (pinfunction "2_2") (pintype "passive"))
    )
    (net (code "82") (name "Net-(C83-Pad2)") (class "Default")
      (node (ref "C83") (pin "2") (pinfunction "2_2") (pintype "passive"))
      (node (ref "D20") (pin "A") (pinfunction "A_A") (pintype "passive"))
      (node (ref "D21") (pin "K") (pinfunction "K_K") (pintype "passive"))
      (node (ref "R134") (pin "2") (pinfunction "2_2") (pintype "passive"))
    )
    (net (code "83") (name "Net-(D1-PadA)") (class "Default")
      (node (ref "D1") (pin "A") (pinfunction "A_A") (pintype "passive"))
      (node (ref "T1") (pin "3") (pinfunction "3_3") (pintype "passive"))
    )
    (net (code "84") (name "Net-(D2-PadA)") (class "Default")
      (node (ref "D2") (pin "A") (pinfunction "A_A") (pintype "passive"))
      (node (ref "T1") (pin "13") (pinfunction "13_13") (pintype "passive"))
    )
    (net (code "85") (name "Net-(D4-PadA)") (class "Default")
      (node (ref "D4") (pin "A") (pinfunction "A_A") (pintype "passive"))
      (node (ref "T1") (pin "11") (pinfunction "11_11") (pintype "passive"))
    )
    (net (code "86") (name "Net-(D5-PadA)") (class "Default")
      (node (ref "D5") (pin "A") (pinfunction "A_A") (pintype "passive"))
      (node (ref "T1") (pin "6") (pinfunction "6_6") (pintype "passive"))
    )
    (net (code "87") (name "Net-(D7-PadA)") (class "Default")
      (node (ref "D7") (pin "A") (pinfunction "A_A") (pintype "passive"))
      (node (ref "T1") (pin "9") (pinfunction "9_9") (pintype "passive"))
    )
    (net (code "88") (name "Net-(D14-PadA)") (class "Default")
      (node (ref "D14") (pin "A") (pinfunction "A_A") (pintype "passive"))
      (node (ref "R111") (pin "2") (pinfunction "2_2") (pintype "passive"))
    )
    (net (code "89") (name "Net-(D19-PadA)") (class "Default")
      (node (ref "D19") (pin "A") (pinfunction "A_A") (pintype "passive"))
      (node (ref "R128") (pin "2") (pinfunction "2_2") (pintype "passive"))
    )
    (net (code "90") (name "Net-(D20-PadK)") (class "Default")
      (node (ref "D20") (pin "K") (pinfunction "K_K") (pintype "passive"))
      (node (ref "PQ1") (pin "1") (pinfunction "1_1") (pintype "passive"))
    )
    (net (code "91") (name "Net-(D22-PadA)") (class "Default")
      (node (ref "D22") (pin "A") (pinfunction "A_A") (pintype "passive"))
      (node (ref "Q8") (pin "G") (pinfunction "G_G") (pintype "input"))
      (node (ref "R108") (pin "2") (pinfunction "2_2") (pintype "passive"))
      (node (ref "R113") (pin "2") (pinfunction "2_2") (pintype "passive"))
    )
    (net (code "92") (name "Net-(D22-PadK)") (class "Default")
      (node (ref "D22") (pin "K") (pinfunction "K_K") (pintype "passive"))
      (node (ref "R146") (pin "2") (pinfunction "2_2") (pintype "passive"))
    )
    (net (code "93") (name "Net-(D23-PadA)") (class "Default")
      (node (ref "D23") (pin "A") (pinfunction "A_A") (pintype "passive"))
      (node (ref "Q9") (pin "G") (pinfunction "G_G") (pintype "input"))
      (node (ref "R109") (pin "2") (pinfunction "2_2") (pintype "passive"))
      (node (ref "R114") (pin "2") (pinfunction "2_2") (pintype "passive"))
    )
    (net (code "94") (name "Net-(D23-PadK)") (class "Default")
      (node (ref "D23") (pin "K") (pinfunction "K_K") (pintype "passive"))
      (node (ref "R147") (pin "2") (pinfunction "2_2") (pintype "passive"))
    )
    (net (code "95") (name "Net-(D24-PadA)") (class "Default")
      (node (ref "D24") (pin "A") (pinfunction "A_A") (pintype "passive"))
      (node (ref "Q13") (pin "G") (pinfunction "G_G") (pintype "input"))
      (node (ref "R123") (pin "2") (pinfunction "2_2") (pintype "passive"))
      (node (ref "R129") (pin "2") (pinfunction "2_2") (pintype "passive"))
    )
    (net (code "96") (name "Net-(D24-PadK)") (class "Default")
      (node (ref "D24") (pin "K") (pinfunction "K_K") (pintype "passive"))
      (node (ref "R148") (pin "2") (pinfunction "2_2") (pintype "passive"))
    )
    (net (code "97") (name "Net-(D25-PadA)") (class "Default")
      (node (ref "D25") (pin "A") (pinfunction "A_A") (pintype "passive"))
      (node (ref "Q14") (pin "G") (pinfunction "G_G") (pintype "input"))
      (node (ref "R124") (pin "2") (pinfunction "2_2") (pintype "passive"))
      (node (ref "R130") (pin "2") (pinfunction "2_2") (pintype "passive"))
    )
    (net (code "98") (name "Net-(D25-PadK)") (class "Default")
      (node (ref "D25") (pin "K") (pinfunction "K_K") (pintype "passive"))
      (node (ref "R149") (pin "2") (pinfunction "2_2") (pintype "passive"))
    )
    (net (code "99") (name "Net-(D26-PadK)") (class "Default")
      (node (ref "D26") (pin "K") (pinfunction "K_K") (pintype "passive"))
      (node (ref "T1") (pin "5") (pinfunction "5_5") (pintype "passive"))
    )
    (net (code "100") (name "Net-(P5-Pad1)") (class "Default")
      (node (ref "P5") (pin "1") (pinfunction "1_1") (pintype "passive"))
      (node (ref "R86") (pin "1") (pinfunction "1_1") (pintype "passive"))
    )
    (net (code "101") (name "Net-(PQ1-Pad4)") (class "Default")
      (node (ref "PQ1") (pin "4") (pinfunction "4_4") (pintype "passive"))
      (node (ref "R136") (pin "1") (pinfunction "1_1") (pintype "passive"))
    )
    (net (code "102") (name "Net-(PQ2-Pad4)") (class "Default")
      (node (ref "PQ2") (pin "4") (pinfunction "4_4") (pintype "passive"))
      (node (ref "R135") (pin "1") (pinfunction "1_1") (pintype "passive"))
      (node (ref "R138") (pin "1") (pinfunction "1_1") (pintype "passive"))
    )
    (net (code "103") (name "Net-(Q1-D)") (class "Default")
      (node (ref "D9") (pin "A") (pinfunction "A_A") (pintype "passive"))
      (node (ref "Q1") (pin "2") (pinfunction "D_2") (pintype "input"))
      (node (ref "T1") (pin "2") (pinfunction "2_2") (pintype "passive"))
    )
    (net (code "104") (name "Net-(Q1-G)") (class "Default")
      (node (ref "Q1") (pin "1") (pinfunction "G_1") (pintype "input"))
      (node (ref "R24") (pin "1") (pinfunction "1_1") (pintype "passive"))
      (node (ref "R25") (pin "2") (pinfunction "2_2") (pintype "passive"))
    )
    (net (code "105") (name "Net-(Q1-S)") (class "Default")
      (node (ref "Q1") (pin "3") (pinfunction "S_3") (pintype "input"))
      (node (ref "R30") (pin "2") (pinfunction "2_2") (pintype "passive"))
      (node (ref "R31") (pin "1") (pinfunction "1_1") (pintype "passive"))
      (node (ref "R32") (pin "1") (pinfunction "1_1") (pintype "passive"))
    )
    (net (code "106") (name "Net-(Q2-B)") (class "Default")
      (node (ref "Q2") (pin "1") (pinfunction "B_1") (pintype "passive"))
      (node (ref "Q3") (pin "3") (pinfunction "C_3") (pintype "passive"))
      (node (ref "R37") (pin "2") (pinfunction "2_2") (pintype "passive"))
      (node (ref "R55") (pin "2") (pinfunction "2_2") (pintype "passive"))
    )
    (net (code "107") (name "Net-(Q3-B)") (class "Default")
      (node (ref "Q3") (pin "1") (pinfunction "B_1") (pintype "passive"))
      (node (ref "R49") (pin "1") (pinfunction "1_1") (pintype "passive"))
      (node (ref "R57") (pin "1") (pinfunction "1_1") (pintype "passive"))
    )
    (net (code "108") (name "Net-(Q15-B)") (class "Default")
      (node (ref "C84") (pin "2") (pinfunction "2_2") (pintype "passive"))
      (node (ref "Q15") (pin "1") (pinfunction "B_1") (pintype "passive"))
      (node (ref "Q16") (pin "3") (pinfunction "C_3") (pintype "passive"))
      (node (ref "R133") (pin "1") (pinfunction "1_1") (pintype "passive"))
    )
    (net (code "109") (name "Net-(Q15-E)") (class "Default")
      (node (ref "Q15") (pin "2") (pinfunction "E_2") (pintype "passive"))
      (node (ref "R140") (pin "2") (pinfunction "2_2") (pintype "passive"))
      (node (ref "R142") (pin "2") (pinfunction "2_2") (pintype "passive"))
      (node (ref "R144") (pin "2") (pinfunction "2_2") (pintype "passive"))
    )
    (net (code "110") (name "Net-(Q16-B)") (class "Default")
      (node (ref "Q16") (pin "1") (pinfunction "B_1") (pintype "passive"))
      (node (ref "R138") (pin "2") (pinfunction "2_2") (pintype "passive"))
    )
    (net (code "111") (name "Net-(Q17-B)") (class "Default")
      (node (ref "PQ1") (pin "3") (pinfunction "3_3") (pintype "passive"))
      (node (ref "Q17") (pin "1") (pinfunction "B_1") (pintype "passive"))
      (node (ref "R141") (pin "2") (pinfunction "2_2") (pintype "passive"))
    )
    (net (code "112") (name "Net-(Q17-C)") (class "Default")
      (node (ref "Q17") (pin "3") (pinfunction "C_3") (pintype "passive"))
      (node (ref "R131") (pin "1") (pinfunction "1_1") (pintype "passive"))
      (node (ref "R137") (pin "2") (pinfunction "2_2") (pintype "passive"))
    )
    (net (code "113") (name "Net-(Q18-B)") (class "Default")
      (node (ref "Q18") (pin "1") (pinfunction "B_1") (pintype "passive"))
      (node (ref "R132") (pin "2") (pinfunction "2_2") (pintype "passive"))
    )
    (net (code "114") (name "Net-(Q18-C)") (class "Default")
      (node (ref "Q18") (pin "3") (pinfunction "C_3") (pintype "passive"))
      (node (ref "R139") (pin "2") (pinfunction "2_2") (pintype "passive"))
    )
    (net (code "115") (name "Net-(Q19-B)") (class "Default")
      (node (ref "Q19") (pin "1") (pinfunction "B_1") (pintype "passive"))
      (node (ref "R145") (pin "1") (pinfunction "1_1") (pintype "passive"))
    )
    (net (code "116") (name "Net-(Q19-C)") (class "Default")
      (node (ref "Q19") (pin "3") (pinfunction "C_3") (pintype "passive"))
      (node (ref "R143") (pin "1") (pinfunction "1_1") (pintype "passive"))
    )
    (net (code "117") (name "Net-(R10-Pad1)") (class "Default")
      (node (ref "R10") (pin "1") (pinfunction "1_1") (pintype "passive"))
      (node (ref "R14") (pin "2") (pinfunction "2_2") (pintype "passive"))
    )
    (net (code "118") (name "Net-(R15-Pad2)") (class "Default")
      (node (ref "R15") (pin "2") (pinfunction "2_2") (pintype "passive"))
      (node (ref "R9") (pin "1") (pinfunction "1_1") (pintype "passive"))
    )
    (net (code "119") (name "Net-(R38-Pad2)") (class "Default")
      (node (ref "R38") (pin "2") (pinfunction "2_2") (pintype "passive"))
      (node (ref "R39") (pin "2") (pinfunction "2_2") (pintype "passive"))
    )
    (net (code "120") (name "Net-(R39-Pad1)") (class "Default")
      (node (ref "R39") (pin "1") (pinfunction "1_1") (pintype "passive"))
      (node (ref "R40") (pin "2") (pinfunction "2_2") (pintype "passive"))
    )
    (net (code "121") (name "Net-(R40-Pad1)") (class "Default")
      (node (ref "R40") (pin "1") (pinfunction "1_1") (pintype "passive"))
      (node (ref "R41") (pin "1") (pinfunction "1_1") (pintype "passive"))
    )
    (net (code "122") (name "Net-(R44-Pad2)") (class "Default")
      (node (ref "R44") (pin "2") (pinfunction "2_2") (pintype "passive"))
      (node (ref "R45") (pin "2") (pinfunction "2_2") (pintype "passive"))
    )
    (net (code "123") (name "Net-(R45-Pad1)") (class "Default")
      (node (ref "R45") (pin "1") (pinfunction "1_1") (pintype "passive"))
      (node (ref "R46") (pin "2") (pinfunction "2_2") (pintype "passive"))
    )
    (net (code "124") (name "Net-(R46-Pad1)") (class "Default")
      (node (ref "R46") (pin "1") (pinfunction "1_1") (pintype "passive"))
      (node (ref "R47") (pin "1") (pinfunction "1_1") (pintype "passive"))
    )
    (net (code "125") (name "Net-(R89-Pad1)") (class "Default")
      (node (ref "R89") (pin "1") (pinfunction "1_1") (pintype "passive"))
      (node (ref "R90") (pin "1") (pinfunction "1_1") (pintype "passive"))
      (node (ref "R91") (pin "1") (pinfunction "1_1") (pintype "passive"))
    )
    (net (code "126") (name "Net-(R96-Pad1)") (class "Default")
      (node (ref "R96") (pin "1") (pinfunction "1_1") (pintype "passive"))
      (node (ref "R97") (pin "2") (pinfunction "2_2") (pintype "passive"))
    )
    (net (code "127") (name "Net-(R97-Pad1)") (class "Default")
      (node (ref "R97") (pin "1") (pinfunction "1_1") (pintype "passive"))
      (node (ref "R98") (pin "2") (pinfunction "2_2") (pintype "passive"))
    )
    (net (code "128") (name "Net-(R107-Pad1)") (class "Default")
      (node (ref "R107") (pin "1") (pinfunction "1_1") (pintype "passive"))
      (node (ref "R112") (pin "2") (pinfunction "2_2") (pintype "passive"))
    )
    (net (code "129") (name "Net-(R112-Pad1)") (class "Default")
      (node (ref "R112") (pin "1") (pinfunction "1_1") (pintype "passive"))
      (node (ref "R115") (pin "2") (pinfunction "2_2") (pintype "passive"))
    )
    (net (code "130") (name "Net-(R119-Pad1)") (class "Default")
      (node (ref "R119") (pin "1") (pinfunction "1_1") (pintype "passive"))
      (node (ref "R120") (pin "2") (pinfunction "2_2") (pintype "passive"))
    )
    (net (code "131") (name "Net-(R120-Pad1)") (class "Default")
      (node (ref "R120") (pin "1") (pinfunction "1_1") (pintype "passive"))
      (node (ref "R121") (pin "2") (pinfunction "2_2") (pintype "passive"))
    )
    (net (code "132") (name "Net-(U1-IN1)") (class "Default")
      (node (ref "R3") (pin "2") (pinfunction "2_2") (pintype "passive"))
      (node (ref "U1") (pin "2") (pinfunction "IN1_2") (pintype "passive"))
    )
    (net (code "133") (name "Net-(U1-IN2)") (class "Default")
      (node (ref "R4") (pin "2") (pinfunction "2_2") (pintype "passive"))
      (node (ref "U1") (pin "3") (pinfunction "IN2_3") (pintype "passive"))
    )
    (net (code "134") (name "Net-(U1-IN3)") (class "Default")
      (node (ref "R5") (pin "2") (pinfunction "2_2") (pintype "passive"))
      (node (ref "U1") (pin "4") (pinfunction "IN3_4") (pintype "passive"))
    )
    (net (code "135") (name "Net-(U1-IN4)") (class "Default")
      (node (ref "R7") (pin "2") (pinfunction "2_2") (pintype "passive"))
      (node (ref "U1") (pin "5") (pinfunction "IN4_5") (pintype "passive"))
    )
    (net (code "136") (name "Net-(U1-OUT1)") (class "Default")
      (node (ref "P1") (pin "4") (pinfunction "4_4") (pintype "passive"))
      (node (ref "U1") (pin "10") (pinfunction "OUT1_10") (pintype "passive"))
    )
    (net (code "137") (name "Net-(U1-OUT2)") (class "Default")
      (node (ref "P1") (pin "1") (pinfunction "1_1") (pintype "passive"))
      (node (ref "U1") (pin "9") (pinfunction "OUT2_9") (pintype "passive"))
    )
    (net (code "138") (name "Net-(U1-OUT3)") (class "Default")
      (node (ref "P1") (pin "3") (pinfunction "3_3") (pintype "passive"))
      (node (ref "U1") (pin "8") (pinfunction "OUT3_8") (pintype "passive"))
    )
    (net (code "139") (name "Net-(U1-OUT4)") (class "Default")
      (node (ref "P1") (pin "2") (pinfunction "2_2") (pintype "passive"))
      (node (ref "U1") (pin "7") (pinfunction "OUT4_7") (pintype "passive"))
    )
    (net (code "140") (name "Net-(U2-In)") (class "Default")
      (node (ref "C6") (pin "2") (pinfunction "2_2") (pintype "passive"))
      (node (ref "R6") (pin "1") (pinfunction "1_1") (pintype "passive"))
      (node (ref "U2") (pin "3") (pinfunction "In_3") (pintype "passive"))
    )
    (net (code "141") (name "Net-(U4-Vout)") (class "Default")
      (node (ref "R150") (pin "2") (pinfunction "2_2") (pintype "passive"))
      (node (ref "R16") (pin "2") (pinfunction "2_2") (pintype "passive"))
      (node (ref "R19") (pin "2") (pinfunction "2_2") (pintype "passive"))
      (node (ref "U4") (pin "2") (pinfunction "Vout_2") (pintype "passive"))
    )
    (net (code "142") (name "Net-(U5-Comp)") (class "Default")
      (node (ref "C13") (pin "2") (pinfunction "2_2") (pintype "passive"))
      (node (ref "R21") (pin "1") (pinfunction "1_1") (pintype "passive"))
      (node (ref "U5") (pin "1") (pinfunction "Comp_1") (pintype "passive"))
    )
    (net (code "143") (name "Net-(U5-Isense)") (class "Default")
      (node (ref "C18") (pin "1") (pinfunction "1_1") (pintype "passive"))
      (node (ref "R30") (pin "1") (pinfunction "1_1") (pintype "passive"))
      (node (ref "U5") (pin "3") (pinfunction "Isense_3") (pintype "passive"))
    )
    (net (code "144") (name "Net-(U5-OUTPUT)") (class "Default")
      (node (ref "R25") (pin "1") (pinfunction "1_1") (pintype "passive"))
      (node (ref "U5") (pin "6") (pinfunction "OUTPUT_6") (pintype "passive"))
    )
    (net (code "145") (name "Net-(U5-RT{slash}CT)") (class "Default")
      (node (ref "C20") (pin "1") (pinfunction "1_1") (pintype "passive"))
      (node (ref "R20") (pin "1") (pinfunction "1_1") (pintype "passive"))
      (node (ref "U5") (pin "4") (pinfunction "RT/CT_4") (pintype "passive"))
    )
    (net (code "146") (name "Net-(U5-VCC)") (class "Default")
      (node (ref "D8") (pin "K") (pinfunction "K_K") (pintype "passive"))
      (node (ref "E13") (pin "1") (pinfunction "1_1") (pintype "passive"))
      (node (ref "R15") (pin "1") (pinfunction "1_1") (pintype "passive"))
      (node (ref "U5") (pin "7") (pinfunction "VCC_7") (pintype "passive"))
    )
    (net (code "147") (name "Net-(U5-Vfb)") (class "Default")
      (node (ref "C13") (pin "1") (pinfunction "1_1") (pintype "passive"))
      (node (ref "R21") (pin "2") (pinfunction "2_2") (pintype "passive"))
      (node (ref "R22") (pin "2") (pinfunction "2_2") (pintype "passive"))
      (node (ref "R23") (pin "1") (pinfunction "1_1") (pintype "passive"))
      (node (ref "U5") (pin "2") (pinfunction "Vfb_2") (pintype "passive"))
    )
    (net (code "148") (name "Net-(U5-Vref)") (class "Default")
      (node (ref "C11") (pin "1") (pinfunction "1_1") (pintype "passive"))
      (node (ref "R20") (pin "2") (pinfunction "2_2") (pintype "passive"))
      (node (ref "U5") (pin "8") (pinfunction "Vref_8") (pintype "passive"))
    )
    (net (code "149") (name "Net-(U6A-IN+)") (class "Default")
      (node (ref "C35") (pin "1") (pinfunction "1_1") (pintype "passive"))
      (node (ref "R61") (pin "2") (pinfunction "2_2") (pintype "passive"))
      (node (ref "R62") (pin "1") (pinfunction "1_1") (pintype "passive"))
      (node (ref "U6") (pin "3") (pinfunction "IN+_3") (pintype "input"))
    )
    (net (code "150") (name "Net-(U6A-IN-)") (class "Default")
      (node (ref "C43") (pin "2") (pinfunction "2_2") (pintype "passive"))
      (node (ref "R65") (pin "2") (pinfunction "2_2") (pintype "passive"))
      (node (ref "R69") (pin "1") (pinfunction "1_1") (pintype "passive"))
      (node (ref "U6") (pin "2") (pinfunction "IN-_2") (pintype "input"))
    )
    (net (code "151") (name "Net-(U6A-OUT)") (class "Default")
      (node (ref "C43") (pin "1") (pinfunction "1_1") (pintype "passive"))
      (node (ref "R63") (pin "1") (pinfunction "1_1") (pintype "passive"))
      (node (ref "R69") (pin "2") (pinfunction "2_2") (pintype "passive"))
      (node (ref "U6") (pin "1") (pinfunction "OUT_1") (pintype "output"))
    )
    (net (code "152") (name "Net-(U6B-IN+)") (class "Default")
      (node (ref "C21") (pin "2") (pinfunction "2_2") (pintype "passive"))
      (node (ref "R28") (pin "1") (pinfunction "1_1") (pintype "passive"))
      (node (ref "R41") (pin "2") (pinfunction "2_2") (pintype "passive"))
      (node (ref "U6") (pin "5") (pinfunction "IN+_5") (pintype "input"))
    )
    (net (code "153") (name "Net-(U6B-IN-)") (class "Default")
      (node (ref "C26") (pin "2") (pinfunction "2_2") (pintype "passive"))
      (node (ref "R47") (pin "2") (pinfunction "2_2") (pintype "passive"))
      (node (ref "R51") (pin "1") (pinfunction "1_1") (pintype "passive"))
      (node (ref "U6") (pin "6") (pinfunction "IN-_6") (pintype "input"))
    )
    (net (code "154") (name "Net-(U7A-IN+)") (class "Default")
      (node (ref "C19") (pin "2") (pinfunction "2_2") (pintype "passive"))
      (node (ref "R33") (pin "2") (pinfunction "2_2") (pintype "passive"))
      (node (ref "R34") (pin "2") (pinfunction "2_2") (pintype "passive"))
      (node (ref "U7") (pin "3") (pinfunction "IN+_3") (pintype "input"))
    )
    (net (code "155") (name "Net-(U7A-IN-)") (class "Default")
      (node (ref "C31") (pin "2") (pinfunction "2_2") (pintype "passive"))
      (node (ref "R48") (pin "2") (pinfunction "2_2") (pintype "passive"))
      (node (ref "R56") (pin "2") (pinfunction "2_2") (pintype "passive"))
      (node (ref "U7") (pin "2") (pinfunction "IN-_2") (pintype "input"))
    )
    (net (code "156") (name "Net-(U7A-OUT)") (class "Default")
      (node (ref "C31") (pin "1") (pinfunction "1_1") (pintype "passive"))
      (node (ref "R43") (pin "2") (pinfunction "2_2") (pintype "passive"))
      (node (ref "R54") (pin "1") (pinfunction "1_1") (pintype "passive"))
      (node (ref "R56") (pin "1") (pinfunction "1_1") (pintype "passive"))
      (node (ref "U7") (pin "1") (pinfunction "OUT_1") (pintype "output"))
    )
    (net (code "157") (name "Net-(U7B-IN+)") (class "Default")
      (node (ref "C15") (pin "1") (pinfunction "1_1") (pintype "passive"))
      (node (ref "R26") (pin "2") (pinfunction "2_2") (pintype "passive"))
      (node (ref "R27") (pin "2") (pinfunction "2_2") (pintype "passive"))
      (node (ref "R36") (pin "1") (pinfunction "1_1") (pintype "passive"))
      (node (ref "U7") (pin "5") (pinfunction "IN+_5") (pintype "input"))
    )
    (net (code "158") (name "Net-(U7B-IN-)") (class "Default")
      (node (ref "C22") (pin "1") (pinfunction "1_1") (pintype "passive"))
      (node (ref "R43") (pin "1") (pinfunction "1_1") (pintype "passive"))
      (node (ref "U7") (pin "6") (pinfunction "IN-_6") (pintype "input"))
    )
    (net (code "159") (name "Net-(U7B-OUT)") (class "Default")
      (node (ref "R27") (pin "1") (pinfunction "1_1") (pintype "passive"))
      (node (ref "R35") (pin "2") (pinfunction "2_2") (pintype "passive"))
      (node (ref "R37") (pin "1") (pinfunction "1_1") (pintype "passive"))
      (node (ref "U7") (pin "7") (pinfunction "OUT_7") (pintype "output"))
    )
    (net (code "160") (name "Net-(U10-VF+)") (class "Default")
      (node (ref "R68") (pin "2") (pinfunction "2_2") (pintype "passive"))
      (node (ref "R70") (pin "2") (pinfunction "2_2") (pintype "passive"))
      (node (ref "U10") (pin "1") (pinfunction "VF+_1") (pintype "passive"))
    )
    (net (code "161") (name "Net-(U11A-IN+)") (class "Default")
      (node (ref "C45") (pin "2") (pinfunction "2_2") (pintype "passive"))
      (node (ref "R73") (pin "2") (pinfunction "2_2") (pintype "passive"))
      (node (ref "R74") (pin "1") (pinfunction "1_1") (pintype "passive"))
      (node (ref "U11") (pin "3") (pinfunction "IN+_3") (pintype "input"))
      (node (ref "U11") (pin "6") (pinfunction "IN-_6") (pintype "input"))
    )
    (net (code "162") (name "Net-(U11A-IN-)") (class "Default")
      (node (ref "C47") (pin "1") (pinfunction "1_1") (pintype "passive"))
      (node (ref "R79") (pin "1") (pinfunction "1_1") (pintype "passive"))
      (node (ref "R81") (pin "2") (pinfunction "2_2") (pintype "passive"))
      (node (ref "U11") (pin "2") (pinfunction "IN-_2") (pintype "input"))
    )
    (net (code "163") (name "Net-(U11A-OUT)") (class "Default")
      (node (ref "R66") (pin "1") (pinfunction "1_1") (pintype "passive"))
      (node (ref "R73") (pin "1") (pinfunction "1_1") (pintype "passive"))
      (node (ref "R80") (pin "1") (pinfunction "1_1") (pintype "passive"))
      (node (ref "U11") (pin "1") (pinfunction "OUT_1") (pintype "output"))
      (node (ref "U11") (pin "7") (pinfunction "OUT_7") (pintype "output"))
    )
    (net (code "164") (name "Net-(U11B-IN+)") (class "Default")
      (node (ref "C42") (pin "2") (pinfunction "2_2") (pintype "passive"))
      (node (ref "R66") (pin "2") (pinfunction "2_2") (pintype "passive"))
      (node (ref "R67") (pin "2") (pinfunction "2_2") (pintype "passive"))
      (node (ref "R71") (pin "2") (pinfunction "2_2") (pintype "passive"))
      (node (ref "U11") (pin "5") (pinfunction "IN+_5") (pintype "input"))
    )
    (net (code "165") (name "Net-(U12-VF+)") (class "Default")
      (node (ref "R75") (pin "2") (pinfunction "2_2") (pintype "passive"))
      (node (ref "R76") (pin "2") (pinfunction "2_2") (pintype "passive"))
      (node (ref "U12") (pin "1") (pinfunction "VF+_1") (pintype "passive"))
    )
    (net (code "166") (name "Net-(U13-VF+)") (class "Default")
      (node (ref "R82") (pin "2") (pinfunction "2_2") (pintype "passive"))
      (node (ref "R83") (pin "2") (pinfunction "2_2") (pintype "passive"))
      (node (ref "U13") (pin "1") (pinfunction "VF+_1") (pintype "passive"))
    )
    (net (code "167") (name "Net-(U14-VF+)") (class "Default")
      (node (ref "R87") (pin "2") (pinfunction "2_2") (pintype "passive"))
      (node (ref "R88") (pin "2") (pinfunction "2_2") (pintype "passive"))
      (node (ref "U14") (pin "1") (pinfunction "VF+_1") (pintype "passive"))
    )
    (net (code "168") (name "PE") (class "Default")
      (node (ref "CY1") (pin "1") (pinfunction "1_1") (pintype "passive"))
      (node (ref "CY2") (pin "2") (pinfunction "2_2") (pintype "passive"))
      (node (ref "P9") (pin "1") (pinfunction "1_1") (pintype "passive"))
    )
    (net (code "169") (name "U_BUS") (class "Default")
      (node (ref "C57") (pin "2") (pinfunction "2_2") (pintype "passive"))
      (node (ref "C58") (pin "2") (pinfunction "2_2") (pintype "passive"))
      (node (ref "C59") (pin "2") (pinfunction "2_2") (pintype "passive"))
      (node (ref "C60") (pin "2") (pinfunction "2_2") (pintype "passive"))
      (node (ref "C84") (pin "1") (pinfunction "1_1") (pintype "passive"))
      (node (ref "E15") (pin "1") (pinfunction "1_1") (pintype "passive"))
      (node (ref "E3") (pin "2") (pinfunction "2_2") (pintype "passive"))
      (node (ref "PQ2") (pin "3") (pinfunction "3_3") (pintype "passive"))
      (node (ref "Q10") (pin "K") (pinfunction "K_K") (pintype "passive"))
      (node (ref "Q11") (pin "K") (pinfunction "K_K") (pintype "passive"))
      (node (ref "Q12") (pin "K") (pinfunction "K_K") (pintype "passive"))
      (node (ref "Q16") (pin "2") (pinfunction "E_2") (pintype "passive"))
      (node (ref "Q8") (pin "D") (pinfunction "D_D") (pintype "input"))
      (node (ref "Q9") (pin "D") (pinfunction "D_D") (pintype "input"))
      (node (ref "R100") (pin "2") (pinfunction "2_2") (pintype "passive"))
      (node (ref "R101") (pin "2") (pinfunction "2_2") (pintype "passive"))
      (node (ref "R102") (pin "2") (pinfunction "2_2") (pintype "passive"))
      (node (ref "R103") (pin "2") (pinfunction "2_2") (pintype "passive"))
      (node (ref "R104") (pin "2") (pinfunction "2_2") (pintype "passive"))
      (node (ref "R105") (pin "2") (pinfunction "2_2") (pintype "passive"))
      (node (ref "R106") (pin "2") (pinfunction "2_2") (pintype "passive"))
      (node (ref "R107") (pin "2") (pinfunction "2_2") (pintype "passive"))
      (node (ref "R96") (pin "2") (pinfunction "2_2") (pintype "passive"))
      (node (ref "R99") (pin "2") (pinfunction "2_2") (pintype "passive"))
      (node (ref "T1") (pin "7") (pinfunction "7_7") (pintype "passive"))
    )
    (net (code "170") (name "U_BUS+") (class "Default")
      (node (ref "R34") (pin "1") (pinfunction "1_1") (pintype "passive"))
      (node (ref "R98") (pin "1") (pinfunction "1_1") (pintype "passive"))
    )
    (net (code "171") (name "U_BUS-") (class "Default")
      (node (ref "R121") (pin "1") (pinfunction "1_1") (pintype "passive"))
      (node (ref "R48") (pin "1") (pinfunction "1_1") (pintype "passive"))
    )
    (net (code "172") (name "V2.5") (class "Default")
      (node (ref "C14") (pin "1") (pinfunction "1_1") (pintype "passive"))
      (node (ref "C21") (pin "1") (pinfunction "1_1") (pintype "passive"))
      (node (ref "C25") (pin "1") (pinfunction "1_1") (pintype "passive"))
      (node (ref "C32") (pin "2") (pinfunction "2_2") (pintype "passive"))
      (node (ref "C35") (pin "2") (pinfunction "2_2") (pintype "passive"))
      (node (ref "R29") (pin "1") (pinfunction "1_1") (pintype "passive"))
      (node (ref "R61") (pin "1") (pinfunction "1_1") (pintype "passive"))
      (node (ref "R92") (pin "1") (pinfunction "1_1") (pintype "passive"))
      (node (ref "U8") (pin "3") (pintype "passive"))
      (node (ref "U8") (pin "4") (pintype "passive"))
    )
    (net (code "173") (name "unconnected-(P13-Pad3)") (class "Default")
      (node (ref "P13") (pin "3") (pinfunction "3_3") (pintype "passive+no_connect"))
    )
    (net (code "174") (name "unconnected-(R16-Pad1)") (class "Default")
      (node (ref "R16") (pin "1") (pinfunction "1_1") (pintype "passive"))
    )
    (net (code "175") (name "unconnected-(R150-Pad1)") (class "Default")
      (node (ref "R150") (pin "1") (pinfunction "1_1") (pintype "passive"))
    )
    (net (code "176") (name "unconnected-(U2-Out-Pad2)") (class "Default")
      (node (ref "U2") (pin "2") (pinfunction "Out_2") (pintype "passive"))
    )
    (net (code "177") (name "unconnected-(U3-P11{slash}TMIOD1-Pad33)") (class "Default")
      (node (ref "U3") (pin "33") (pinfunction "P11/TMIOD1_33") (pintype "passive+no_connect"))
    )
    (net (code "178") (name "unconnected-(U3-P16{slash}TMIOC0-Pad28)") (class "Default")
      (node (ref "U3") (pin "28") (pinfunction "P16/TMIOC0_28") (pintype "passive+no_connect"))
    )
    (net (code "179") (name "unconnected-(U3-P17{slash}TXD0{slash}TMIOA0{slash}TI02-Pad27)") (class "Default")
      (node (ref "U3") (pin "27") (pinfunction "P17/TXD0/TMIOA0/TI02_27") (pintype "passive+no_connect"))
    )
    (net (code "180") (name "unconnected-(U3-P21{slash}ANI1AVREFM{slash}VCIN13-Pad43)") (class "Default")
      (node (ref "U3") (pin "43") (pinfunction "P21/ANI1AVREFM/VCIN13_43") (pintype "passive+no_connect"))
    )
    (net (code "181") (name "unconnected-(U3-P41{slash}(TAI0)-Pad2)") (class "Default")
      (node (ref "U3") (pin "2") (pinfunction "P41/(TAI0)_2") (pintype "passive+no_connect"))
    )
    (net (code "182") (name "unconnected-(U3-P51{slash}INTP2{slash}TXD0{slash}TBIO1-Pad26)") (class "Default")
      (node (ref "U3") (pin "26") (pinfunction "P51/INTP2/TXD0/TBIO1_26") (pintype "passive+no_connect"))
    )
    (net (code "183") (name "unconnected-(U3-P62{slash}S00-Pad15)") (class "Default")
      (node (ref "U3") (pin "15") (pinfunction "P62/S00_15") (pintype "passive+no_connect"))
    )
    (net (code "184") (name "unconnected-(U3-P63-Pad16)") (class "Default")
      (node (ref "U3") (pin "16") (pinfunction "P63_16") (pintype "passive+no_connect"))
    )
    (net (code "185") (name "unconnected-(U3-P70{slash}(VCOUT1)-Pad23)") (class "Default")
      (node (ref "U3") (pin "23") (pinfunction "P70/(VCOUT1)_23") (pintype "passive+no_connect"))
    )
    (net (code "186") (name "unconnected-(U3-P71{slash}(VCOUT0）-Pad22)") (class "Default")
      (node (ref "U3") (pin "22") (pinfunction "P71/(VCOUT0）_22") (pintype "passive+no_connect"))
    )
    (net (code "187") (name "unconnected-(U3-P73{slash}(RXD1)-Pad20)") (class "Default")
      (node (ref "U3") (pin "20") (pinfunction "P73/(RXD1)_20") (pintype "passive+no_connect"))
    )
    (net (code "188") (name "unconnected-(U3-P75{slash}INTP9{slash}SCLK01{slash}SCL01-Pad18)") (class "Default")
      (node (ref "U3") (pin "18") (pinfunction "P75/INTP9/SCLK01/SCL01_18") (pintype "passive+no_connect"))
    )
    (net (code "189") (name "unconnected-(U3-P120{slash}ANI14{slash}VCOUT0-Pad1)") (class "Default")
      (node (ref "U3") (pin "1") (pinfunction "P120/ANI14/VCOUT0_1") (pintype "passive+no_connect"))
    )
    (net (code "190") (name "unconnected-(U3-P123{slash}XT1-Pad6)") (class "Default")
      (node (ref "U3") (pin "6") (pinfunction "P123/XT1_6") (pintype "passive+no_connect"))
    )
    (net (code "191") (name "unconnected-(U3-P124{slash}XT2-Pad5)") (class "Default")
      (node (ref "U3") (pin "5") (pinfunction "P124/XT2_5") (pintype "passive+no_connect"))
    )
    (net (code "192") (name "unconnected-(U3-P130-Pad45)") (class "Default")
      (node (ref "U3") (pin "45") (pinfunction "P130_45") (pintype "passive+no_connect"))
    )
    (net (code "193") (name "unconnected-(U3-P140{slash}INTP6-Pad48)") (class "Default")
      (node (ref "U3") (pin "48") (pinfunction "P140/INTP6_48") (pintype "passive+no_connect"))
    )
    (net (code "194") (name "unconnected-(U3-P147{slash}ANI12{slash}VREF0-Pad36)") (class "Default")
      (node (ref "U3") (pin "36") (pinfunction "P147/ANI12/VREF0_36") (pintype "passive+no_connect"))
    )
    (net (code "195") (name "unconnected-(U10-NC-Pad2)") (class "Default")
      (node (ref "U10") (pin "2") (pinfunction "NC_2") (pintype "passive+no_connect"))
    )
    (net (code "196") (name "unconnected-(U12-NC-Pad2)") (class "Default")
      (node (ref "U12") (pin "2") (pinfunction "NC_2") (pintype "passive+no_connect"))
    )
    (net (code "197") (name "unconnected-(U13-NC-Pad2)") (class "Default")
      (node (ref "U13") (pin "2") (pinfunction "NC_2") (pintype "passive+no_connect"))
    )
    (net (code "198") (name "unconnected-(U14-NC-Pad2)") (class "Default")
      (node (ref "U14") (pin "2") (pinfunction "NC_2") (pintype "passive+no_connect"))
    )
  )
)
